# Main.net
KiCad netlist of a schematic drawn in Altium Designer
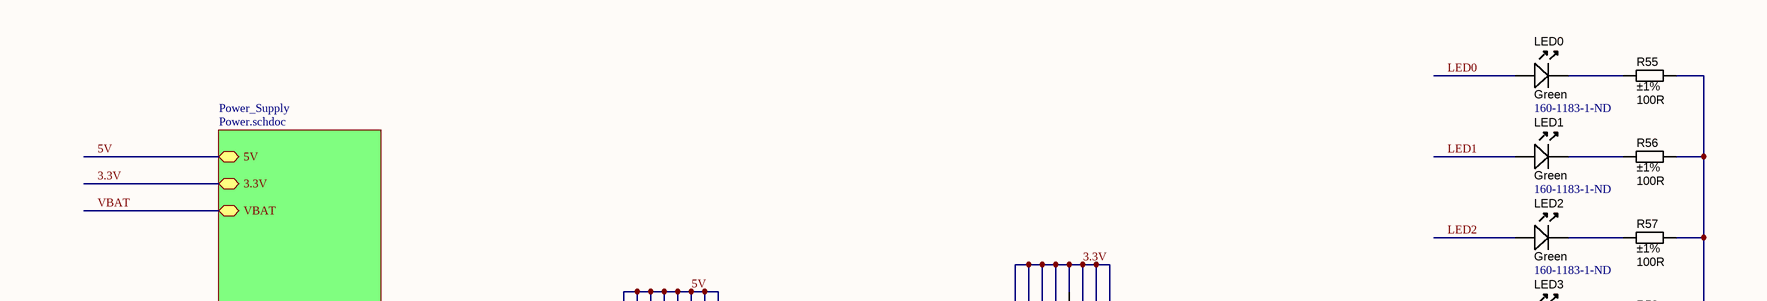
[diagram p0: Main.SchDoc, top right]
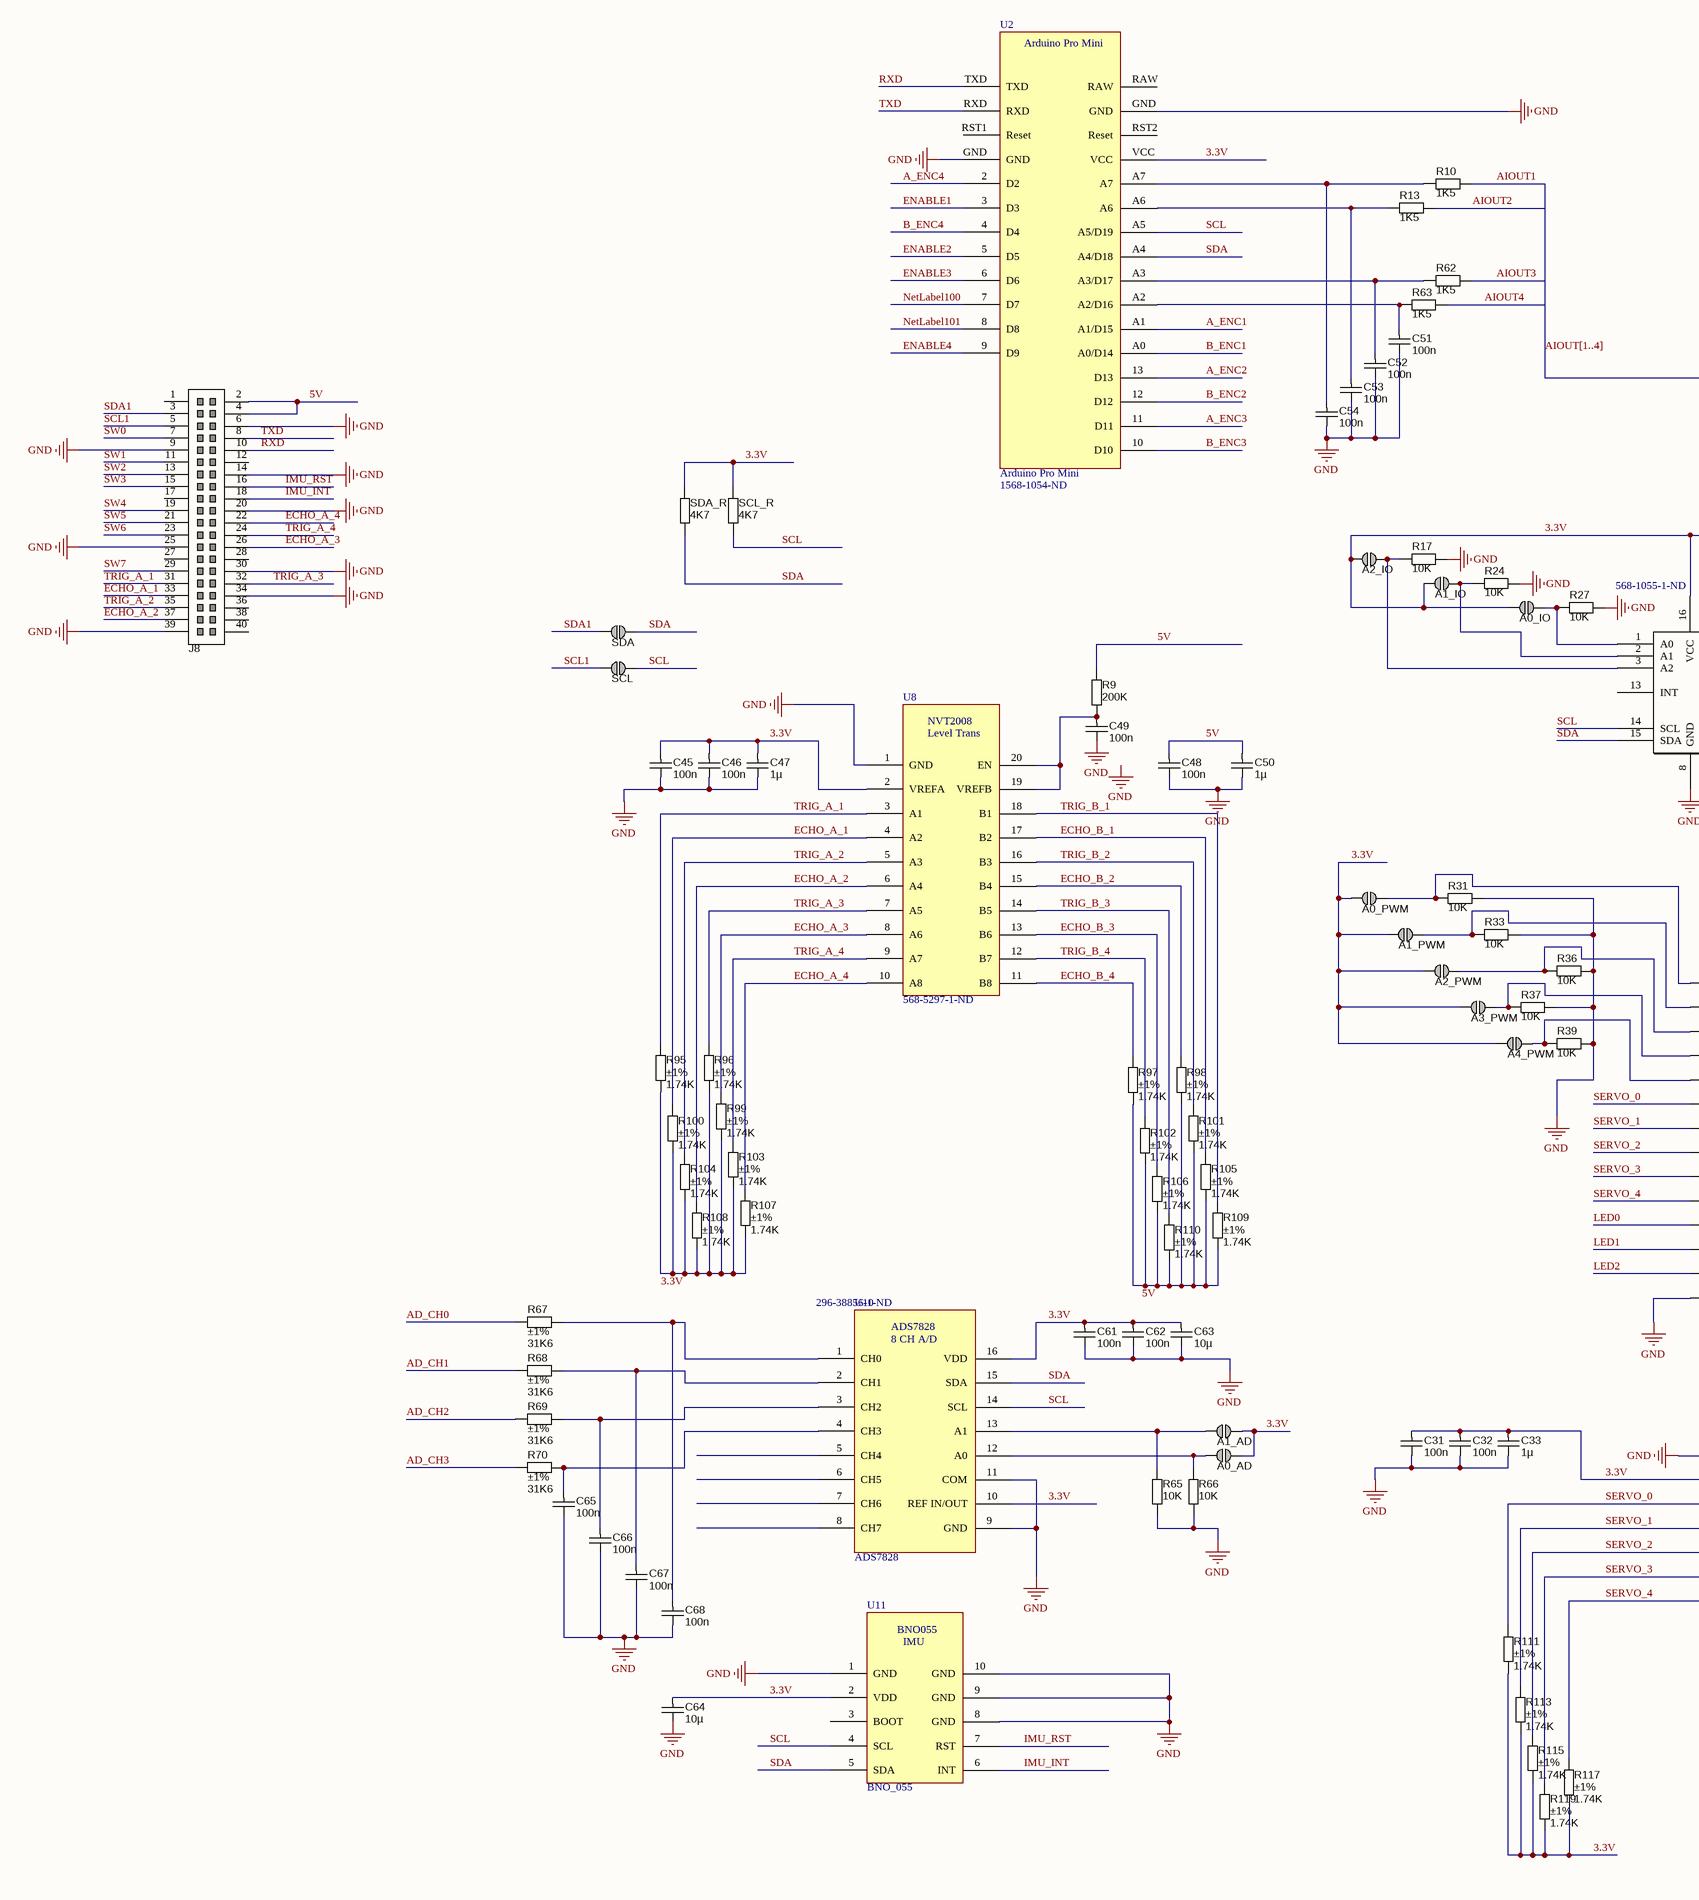
[diagram p1: Main.SchDoc, bottom left]
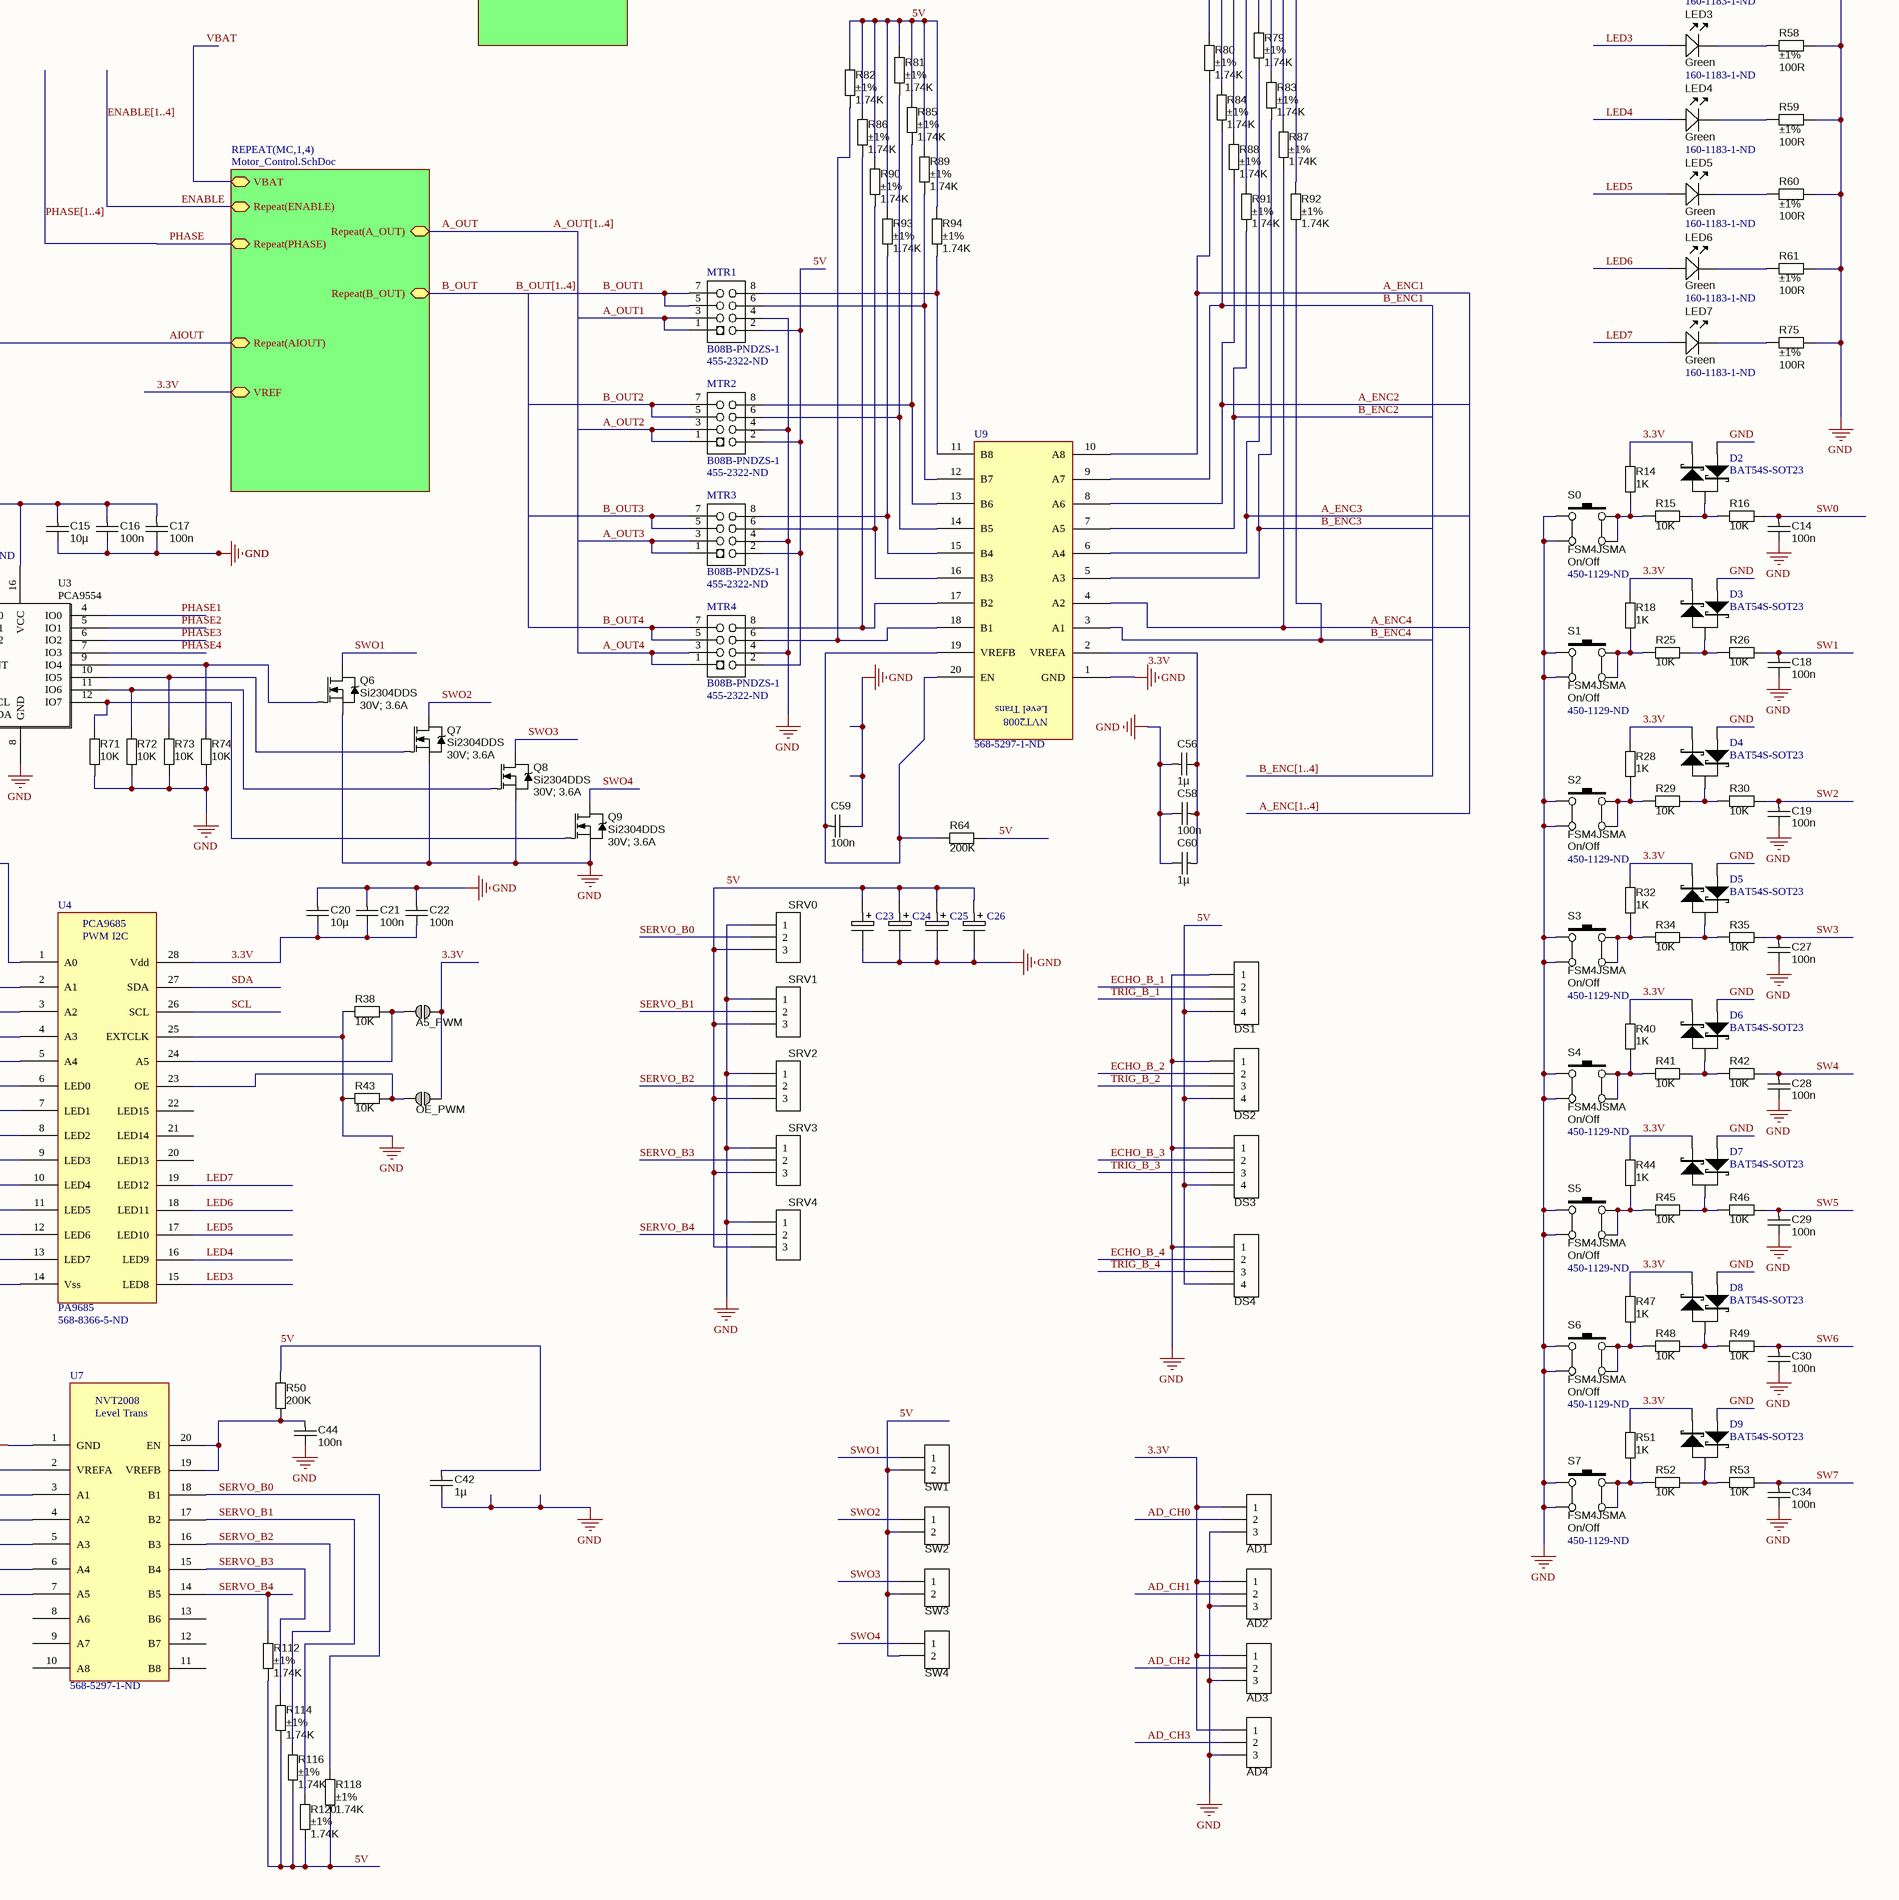
[diagram p2: Main.SchDoc, bottom right]

(export (version "E")
  (design (tool "Eeschema 10.0.6"))
  (components
    (comp (ref "A0_AD")
      (value "Jumper")
      (footprint "JUMP1")
      (description "SMD jumper")
      (libsource (lib "PBL - Pads and Jumpers") (part "JUMP1"))
    )
    (comp (ref "A0_IO")
      (value "Jumper")
      (footprint "JUMP1")
      (description "SMD jumper")
      (libsource (lib "PBL - Pads and Jumpers") (part "JUMP1"))
    )
    (comp (ref "A0_PWM")
      (value "Jumper")
      (footprint "JUMP1")
      (description "SMD jumper")
      (libsource (lib "PBL - Pads and Jumpers") (part "JUMP1"))
    )
    (comp (ref "A1_AD")
      (value "Jumper")
      (footprint "JUMP1")
      (description "SMD jumper")
      (libsource (lib "PBL - Pads and Jumpers") (part "JUMP1"))
    )
    (comp (ref "A1_IO")
      (value "Jumper")
      (footprint "JUMP1")
      (description "SMD jumper")
      (libsource (lib "PBL - Pads and Jumpers") (part "JUMP1"))
    )
    (comp (ref "A1_PWM")
      (value "Jumper")
      (footprint "JUMP1")
      (description "SMD jumper")
      (libsource (lib "PBL - Pads and Jumpers") (part "JUMP1"))
    )
    (comp (ref "A2_IO")
      (value "Jumper")
      (footprint "JUMP1")
      (description "SMD jumper")
      (libsource (lib "PBL - Pads and Jumpers") (part "JUMP1"))
    )
    (comp (ref "A2_PWM")
      (value "Jumper")
      (footprint "JUMP1")
      (description "SMD jumper")
      (libsource (lib "PBL - Pads and Jumpers") (part "JUMP1"))
    )
    (comp (ref "A3_PWM")
      (value "Jumper")
      (footprint "JUMP1")
      (description "SMD jumper")
      (libsource (lib "PBL - Pads and Jumpers") (part "JUMP1"))
    )
    (comp (ref "A4_PWM")
      (value "Jumper")
      (footprint "JUMP1")
      (description "SMD jumper")
      (libsource (lib "PBL - Pads and Jumpers") (part "JUMP1"))
    )
    (comp (ref "A5_PWM")
      (value "Jumper")
      (footprint "JUMP1")
      (description "SMD jumper")
      (libsource (lib "PBL - Pads and Jumpers") (part "JUMP1"))
    )
    (comp (ref "AD1")
      (value "JST_PH_B3B")
      (footprint "JST_PH_3_B3B")
      (description "2mm Pitch")
      (libsource (lib "PBL - Connectors") (part "JST_PH_B3B"))
    )
    (comp (ref "AD2")
      (value "JST_PH_B3B")
      (footprint "JST_PH_3_B3B")
      (description "2mm Pitch")
      (libsource (lib "PBL - Connectors") (part "JST_PH_B3B"))
    )
    (comp (ref "AD3")
      (value "JST_PH_B3B")
      (footprint "JST_PH_3_B3B")
      (description "2mm Pitch")
      (libsource (lib "PBL - Connectors") (part "JST_PH_B3B"))
    )
    (comp (ref "AD4")
      (value "JST_PH_B3B")
      (footprint "JST_PH_3_B3B")
      (description "2mm Pitch")
      (libsource (lib "PBL - Connectors") (part "JST_PH_B3B"))
    )
    (comp (ref "C14")
      (value "100n")
      (footprint "CAPC1608X90N")
      (description "Capacitor SMD Cer 100nF 10% 50V X7R 0603")
      (fields (field (name "TOLERANCE") "±10%") (field (name "Comment") "approved sub OK"))
      (libsource (lib "PBL - Capacitors") (part "CAPC_100n_0603_X7R_50V_10%"))
    )
    (comp (ref "C15")
      (value "10µ")
      (footprint "CAPC2012X135N")
      (description "Capacitor SMD Cer 10uF 10% 10V X5R 0805")
      (fields (field (name "TOLERANCE") "±10%") (field (name "Comment") "approved sub OK"))
      (libsource (lib "PBL - Capacitors") (part "CAPC_10u_0805_10V"))
    )
    (comp (ref "C16")
      (value "100n")
      (footprint "CAPC1608X90N")
      (description "Capacitor SMD Cer 100nF 10% 50V X7R 0603")
      (fields (field (name "TOLERANCE") "±10%") (field (name "Comment") "approved sub OK"))
      (libsource (lib "PBL - Capacitors") (part "CAPC_100n_0603_X7R_50V_10%"))
    )
    (comp (ref "C17")
      (value "100n")
      (footprint "CAPC1608X90N")
      (description "Capacitor SMD Cer 100nF 10% 50V X7R 0603")
      (fields (field (name "TOLERANCE") "±10%") (field (name "Comment") "approved sub OK"))
      (libsource (lib "PBL - Capacitors") (part "CAPC_100n_0603_X7R_50V_10%"))
    )
    (comp (ref "C18")
      (value "100n")
      (footprint "CAPC1608X90N")
      (description "Capacitor SMD Cer 100nF 10% 50V X7R 0603")
      (fields (field (name "TOLERANCE") "±10%") (field (name "Comment") "approved sub OK"))
      (libsource (lib "PBL - Capacitors") (part "CAPC_100n_0603_X7R_50V_10%"))
    )
    (comp (ref "C19")
      (value "100n")
      (footprint "CAPC1608X90N")
      (description "Capacitor SMD Cer 100nF 10% 50V X7R 0603")
      (fields (field (name "TOLERANCE") "±10%") (field (name "Comment") "approved sub OK"))
      (libsource (lib "PBL - Capacitors") (part "CAPC_100n_0603_X7R_50V_10%"))
    )
    (comp (ref "C20")
      (value "10µ")
      (footprint "CAPC2012X135N")
      (description "Capacitor SMD Cer 10uF 10% 10V X5R 0805")
      (fields (field (name "TOLERANCE") "±10%") (field (name "Comment") "approved sub OK"))
      (libsource (lib "PBL - Capacitors") (part "CAPC_10u_0805_10V"))
    )
    (comp (ref "C21")
      (value "100n")
      (footprint "CAPC1608X90N")
      (description "Capacitor SMD Cer 100nF 10% 50V X7R 0603")
      (fields (field (name "TOLERANCE") "±10%") (field (name "Comment") "approved sub OK"))
      (libsource (lib "PBL - Capacitors") (part "CAPC_100n_0603_X7R_50V_10%"))
    )
    (comp (ref "C22")
      (value "100n")
      (footprint "CAPC1608X90N")
      (description "Capacitor SMD Cer 100nF 10% 50V X7R 0603")
      (fields (field (name "TOLERANCE") "±10%") (field (name "Comment") "approved sub OK"))
      (libsource (lib "PBL - Capacitors") (part "CAPC_100n_0603_X7R_50V_10%"))
    )
    (comp (ref "C23")
      (value "UUD1C221MCL1GS")
      (footprint "NICH 6.3mm 7.7mm")
      (description "GENERIC CAPACITOR POLARISED")
      (libsource (lib "SMD Capacitors Electrolytic") (part "NICHICON_220uF_16V"))
    )
    (comp (ref "C24")
      (value "UUD1C221MCL1GS")
      (footprint "NICH 6.3mm 7.7mm")
      (description "GENERIC CAPACITOR POLARISED")
      (libsource (lib "SMD Capacitors Electrolytic") (part "NICHICON_220uF_16V"))
    )
    (comp (ref "C25")
      (value "UUD1C221MCL1GS")
      (footprint "NICH 6.3mm 7.7mm")
      (description "GENERIC CAPACITOR POLARISED")
      (libsource (lib "SMD Capacitors Electrolytic") (part "NICHICON_220uF_16V"))
    )
    (comp (ref "C26")
      (value "UUD1C221MCL1GS")
      (footprint "NICH 6.3mm 7.7mm")
      (description "GENERIC CAPACITOR POLARISED")
      (libsource (lib "SMD Capacitors Electrolytic") (part "NICHICON_220uF_16V"))
    )
    (comp (ref "C27")
      (value "100n")
      (footprint "CAPC1608X90N")
      (description "Capacitor SMD Cer 100nF 10% 50V X7R 0603")
      (fields (field (name "TOLERANCE") "±10%") (field (name "Comment") "approved sub OK"))
      (libsource (lib "PBL - Capacitors") (part "CAPC_100n_0603_X7R_50V_10%"))
    )
    (comp (ref "C28")
      (value "100n")
      (footprint "CAPC1608X90N")
      (description "Capacitor SMD Cer 100nF 10% 50V X7R 0603")
      (fields (field (name "TOLERANCE") "±10%") (field (name "Comment") "approved sub OK"))
      (libsource (lib "PBL - Capacitors") (part "CAPC_100n_0603_X7R_50V_10%"))
    )
    (comp (ref "C29")
      (value "100n")
      (footprint "CAPC1608X90N")
      (description "Capacitor SMD Cer 100nF 10% 50V X7R 0603")
      (fields (field (name "TOLERANCE") "±10%") (field (name "Comment") "approved sub OK"))
      (libsource (lib "PBL - Capacitors") (part "CAPC_100n_0603_X7R_50V_10%"))
    )
    (comp (ref "C30")
      (value "100n")
      (footprint "CAPC1608X90N")
      (description "Capacitor SMD Cer 100nF 10% 50V X7R 0603")
      (fields (field (name "TOLERANCE") "±10%") (field (name "Comment") "approved sub OK"))
      (libsource (lib "PBL - Capacitors") (part "CAPC_100n_0603_X7R_50V_10%"))
    )
    (comp (ref "C31")
      (value "100n")
      (footprint "CAPC1608X90N")
      (description "Capacitor SMD Cer 100nF 10% 50V X7R 0603")
      (fields (field (name "TOLERANCE") "±10%") (field (name "Comment") "approved sub OK"))
      (libsource (lib "PBL - Capacitors") (part "CAPC_100n_0603_X7R_50V_10%"))
    )
    (comp (ref "C32")
      (value "100n")
      (footprint "CAPC1608X90N")
      (description "Capacitor SMD Cer 100nF 10% 50V X7R 0603")
      (fields (field (name "TOLERANCE") "±10%") (field (name "Comment") "approved sub OK"))
      (libsource (lib "PBL - Capacitors") (part "CAPC_100n_0603_X7R_50V_10%"))
    )
    (comp (ref "C33")
      (value "1µ")
      (footprint "CAPC1608X90N")
      (description "Capacitor SMD Cer 1uF 10% 16V X7R 0603")
      (fields (field (name "TOLERANCE") "±10%") (field (name "Comment") "approved sub OK"))
      (libsource (lib "PBL - Capacitors") (part "CAPC_1u_0603_X7R_16V_10%"))
    )
    (comp (ref "C34")
      (value "100n")
      (footprint "CAPC1608X90N")
      (description "Capacitor SMD Cer 100nF 10% 50V X7R 0603")
      (fields (field (name "TOLERANCE") "±10%") (field (name "Comment") "approved sub OK"))
      (libsource (lib "PBL - Capacitors") (part "CAPC_100n_0603_X7R_50V_10%"))
    )
    (comp (ref "C42")
      (value "1µ")
      (footprint "CAPC1608X90N")
      (description "Capacitor SMD Cer 1uF 10% 16V X7R 0603")
      (fields (field (name "TOLERANCE") "±10%") (field (name "Comment") "approved sub OK"))
      (libsource (lib "PBL - Capacitors") (part "CAPC_1u_0603_X7R_16V_10%"))
    )
    (comp (ref "C44")
      (value "100n")
      (footprint "CAPC1608X90N")
      (description "Capacitor SMD Cer 100nF 10% 50V X7R 0603")
      (fields (field (name "TOLERANCE") "±10%") (field (name "Comment") "approved sub OK"))
      (libsource (lib "PBL - Capacitors") (part "CAPC_100n_0603_X7R_50V_10%"))
    )
    (comp (ref "C45")
      (value "100n")
      (footprint "CAPC1608X90N")
      (description "Capacitor SMD Cer 100nF 10% 50V X7R 0603")
      (fields (field (name "TOLERANCE") "±10%") (field (name "Comment") "approved sub OK"))
      (libsource (lib "PBL - Capacitors") (part "CAPC_100n_0603_X7R_50V_10%"))
    )
    (comp (ref "C46")
      (value "100n")
      (footprint "CAPC1608X90N")
      (description "Capacitor SMD Cer 100nF 10% 50V X7R 0603")
      (fields (field (name "TOLERANCE") "±10%") (field (name "Comment") "approved sub OK"))
      (libsource (lib "PBL - Capacitors") (part "CAPC_100n_0603_X7R_50V_10%"))
    )
    (comp (ref "C47")
      (value "1µ")
      (footprint "CAPC1608X90N")
      (description "Capacitor SMD Cer 1uF 10% 16V X7R 0603")
      (fields (field (name "TOLERANCE") "±10%") (field (name "Comment") "approved sub OK"))
      (libsource (lib "PBL - Capacitors") (part "CAPC_1u_0603_X7R_16V_10%"))
    )
    (comp (ref "C48")
      (value "100n")
      (footprint "CAPC1608X90N")
      (description "Capacitor SMD Cer 100nF 10% 50V X7R 0603")
      (fields (field (name "TOLERANCE") "±10%") (field (name "Comment") "approved sub OK"))
      (libsource (lib "PBL - Capacitors") (part "CAPC_100n_0603_X7R_50V_10%"))
    )
    (comp (ref "C49")
      (value "100n")
      (footprint "CAPC1608X90N")
      (description "Capacitor SMD Cer 100nF 10% 50V X7R 0603")
      (fields (field (name "TOLERANCE") "±10%") (field (name "Comment") "approved sub OK"))
      (libsource (lib "PBL - Capacitors") (part "CAPC_100n_0603_X7R_50V_10%"))
    )
    (comp (ref "C50")
      (value "1µ")
      (footprint "CAPC1608X90N")
      (description "Capacitor SMD Cer 1uF 10% 16V X7R 0603")
      (fields (field (name "TOLERANCE") "±10%") (field (name "Comment") "approved sub OK"))
      (libsource (lib "PBL - Capacitors") (part "CAPC_1u_0603_X7R_16V_10%"))
    )
    (comp (ref "C51")
      (value "100n")
      (footprint "CAPC1608X90N")
      (description "Capacitor SMD Cer 100nF 10% 50V X7R 0603")
      (fields (field (name "TOLERANCE") "±10%") (field (name "Comment") "approved sub OK"))
      (libsource (lib "PBL - Capacitors") (part "CAPC_100n_0603_X7R_50V_10%"))
    )
    (comp (ref "C52")
      (value "100n")
      (footprint "CAPC1608X90N")
      (description "Capacitor SMD Cer 100nF 10% 50V X7R 0603")
      (fields (field (name "TOLERANCE") "±10%") (field (name "Comment") "approved sub OK"))
      (libsource (lib "PBL - Capacitors") (part "CAPC_100n_0603_X7R_50V_10%"))
    )
    (comp (ref "C53")
      (value "100n")
      (footprint "CAPC1608X90N")
      (description "Capacitor SMD Cer 100nF 10% 50V X7R 0603")
      (fields (field (name "TOLERANCE") "±10%") (field (name "Comment") "approved sub OK"))
      (libsource (lib "PBL - Capacitors") (part "CAPC_100n_0603_X7R_50V_10%"))
    )
    (comp (ref "C54")
      (value "100n")
      (footprint "CAPC1608X90N")
      (description "Capacitor SMD Cer 100nF 10% 50V X7R 0603")
      (fields (field (name "TOLERANCE") "±10%") (field (name "Comment") "approved sub OK"))
      (libsource (lib "PBL - Capacitors") (part "CAPC_100n_0603_X7R_50V_10%"))
    )
    (comp (ref "C56")
      (value "1µ")
      (footprint "CAPC1608X90N")
      (description "Capacitor SMD Cer 1uF 10% 16V X7R 0603")
      (fields (field (name "TOLERANCE") "±10%") (field (name "Comment") "approved sub OK"))
      (libsource (lib "PBL - Capacitors") (part "CAPC_1u_0603_X7R_16V_10%"))
    )
    (comp (ref "C58")
      (value "100n")
      (footprint "CAPC1608X90N")
      (description "Capacitor SMD Cer 100nF 10% 50V X7R 0603")
      (fields (field (name "TOLERANCE") "±10%") (field (name "Comment") "approved sub OK"))
      (libsource (lib "PBL - Capacitors") (part "CAPC_100n_0603_X7R_50V_10%"))
    )
    (comp (ref "C59")
      (value "100n")
      (footprint "CAPC1608X90N")
      (description "Capacitor SMD Cer 100nF 10% 50V X7R 0603")
      (fields (field (name "TOLERANCE") "±10%") (field (name "Comment") "approved sub OK"))
      (libsource (lib "PBL - Capacitors") (part "CAPC_100n_0603_X7R_50V_10%"))
    )
    (comp (ref "C60")
      (value "1µ")
      (footprint "CAPC1608X90N")
      (description "Capacitor SMD Cer 1uF 10% 16V X7R 0603")
      (fields (field (name "TOLERANCE") "±10%") (field (name "Comment") "approved sub OK"))
      (libsource (lib "PBL - Capacitors") (part "CAPC_1u_0603_X7R_16V_10%"))
    )
    (comp (ref "C61")
      (value "100n")
      (footprint "CAPC1608X90N")
      (description "Capacitor SMD Cer 100nF 10% 50V X7R 0603")
      (fields (field (name "TOLERANCE") "±10%") (field (name "Comment") "approved sub OK"))
      (libsource (lib "PBL - Capacitors") (part "CAPC_100n_0603_X7R_50V_10%"))
    )
    (comp (ref "C62")
      (value "100n")
      (footprint "CAPC1608X90N")
      (description "Capacitor SMD Cer 100nF 10% 50V X7R 0603")
      (fields (field (name "TOLERANCE") "±10%") (field (name "Comment") "approved sub OK"))
      (libsource (lib "PBL - Capacitors") (part "CAPC_100n_0603_X7R_50V_10%"))
    )
    (comp (ref "C63")
      (value "10µ")
      (footprint "CAPC2012X135N")
      (description "Capacitor SMD Cer 10uF 10% 10V X5R 0805")
      (fields (field (name "TOLERANCE") "±10%") (field (name "Comment") "approved sub OK"))
      (libsource (lib "PBL - Capacitors") (part "CAPC_10u_0805_10V"))
    )
    (comp (ref "C64")
      (value "10µ")
      (footprint "CAPC2012X135N")
      (description "Capacitor SMD Cer 10uF 10% 10V X5R 0805")
      (fields (field (name "TOLERANCE") "±10%") (field (name "Comment") "approved sub OK"))
      (libsource (lib "PBL - Capacitors") (part "CAPC_10u_0805_10V"))
    )
    (comp (ref "C65")
      (value "100n")
      (footprint "CAPC1608X90N")
      (description "Capacitor SMD Cer 100nF 10% 50V X7R 0603")
      (fields (field (name "TOLERANCE") "±10%") (field (name "Comment") "approved sub OK"))
      (libsource (lib "PBL - Capacitors") (part "CAPC_100n_0603_X7R_50V_10%"))
    )
    (comp (ref "C66")
      (value "100n")
      (footprint "CAPC1608X90N")
      (description "Capacitor SMD Cer 100nF 10% 50V X7R 0603")
      (fields (field (name "TOLERANCE") "±10%") (field (name "Comment") "approved sub OK"))
      (libsource (lib "PBL - Capacitors") (part "CAPC_100n_0603_X7R_50V_10%"))
    )
    (comp (ref "C67")
      (value "100n")
      (footprint "CAPC1608X90N")
      (description "Capacitor SMD Cer 100nF 10% 50V X7R 0603")
      (fields (field (name "TOLERANCE") "±10%") (field (name "Comment") "approved sub OK"))
      (libsource (lib "PBL - Capacitors") (part "CAPC_100n_0603_X7R_50V_10%"))
    )
    (comp (ref "C68")
      (value "100n")
      (footprint "CAPC1608X90N")
      (description "Capacitor SMD Cer 100nF 10% 50V X7R 0603")
      (fields (field (name "TOLERANCE") "±10%") (field (name "Comment") "approved sub OK"))
      (libsource (lib "PBL - Capacitors") (part "CAPC_100n_0603_X7R_50V_10%"))
    )
    (comp (ref "D2")
      (value "BAT54S-SOT23")
      (footprint "SOT23-123")
      (description "DUAL SCHOTTKY DIODE SERIES")
      (fields
        (field (name "MANUFACTURER PART NUMBER") "BAT54S,215")
        (field (name "MANUFACTURER") "NXP Semiconductors")
      )
      (libsource (lib "SMD Diodes") (part "BAT54S-SOT23"))
    )
    (comp (ref "D3")
      (value "BAT54S-SOT23")
      (footprint "SOT23-123")
      (description "DUAL SCHOTTKY DIODE SERIES")
      (fields
        (field (name "MANUFACTURER PART NUMBER") "BAT54S,215")
        (field (name "MANUFACTURER") "NXP Semiconductors")
      )
      (libsource (lib "SMD Diodes") (part "BAT54S-SOT23"))
    )
    (comp (ref "D4")
      (value "BAT54S-SOT23")
      (footprint "SOT23-123")
      (description "DUAL SCHOTTKY DIODE SERIES")
      (fields
        (field (name "MANUFACTURER PART NUMBER") "BAT54S,215")
        (field (name "MANUFACTURER") "NXP Semiconductors")
      )
      (libsource (lib "SMD Diodes") (part "BAT54S-SOT23"))
    )
    (comp (ref "D5")
      (value "BAT54S-SOT23")
      (footprint "SOT23-123")
      (description "DUAL SCHOTTKY DIODE SERIES")
      (fields
        (field (name "MANUFACTURER PART NUMBER") "BAT54S,215")
        (field (name "MANUFACTURER") "NXP Semiconductors")
      )
      (libsource (lib "SMD Diodes") (part "BAT54S-SOT23"))
    )
    (comp (ref "D6")
      (value "BAT54S-SOT23")
      (footprint "SOT23-123")
      (description "DUAL SCHOTTKY DIODE SERIES")
      (fields
        (field (name "MANUFACTURER PART NUMBER") "BAT54S,215")
        (field (name "MANUFACTURER") "NXP Semiconductors")
      )
      (libsource (lib "SMD Diodes") (part "BAT54S-SOT23"))
    )
    (comp (ref "D7")
      (value "BAT54S-SOT23")
      (footprint "SOT23-123")
      (description "DUAL SCHOTTKY DIODE SERIES")
      (fields
        (field (name "MANUFACTURER PART NUMBER") "BAT54S,215")
        (field (name "MANUFACTURER") "NXP Semiconductors")
      )
      (libsource (lib "SMD Diodes") (part "BAT54S-SOT23"))
    )
    (comp (ref "D8")
      (value "BAT54S-SOT23")
      (footprint "SOT23-123")
      (description "DUAL SCHOTTKY DIODE SERIES")
      (fields
        (field (name "MANUFACTURER PART NUMBER") "BAT54S,215")
        (field (name "MANUFACTURER") "NXP Semiconductors")
      )
      (libsource (lib "SMD Diodes") (part "BAT54S-SOT23"))
    )
    (comp (ref "D9")
      (value "BAT54S-SOT23")
      (footprint "SOT23-123")
      (description "DUAL SCHOTTKY DIODE SERIES")
      (fields
        (field (name "MANUFACTURER PART NUMBER") "BAT54S,215")
        (field (name "MANUFACTURER") "NXP Semiconductors")
      )
      (libsource (lib "SMD Diodes") (part "BAT54S-SOT23"))
    )
    (comp (ref "DS1")
      (value "JST_PH_B4B")
      (footprint "JST_PH_4_B4B")
      (description "2mm Pitch")
      (libsource (lib "PBL - Connectors") (part "JST_PH_B4B"))
    )
    (comp (ref "DS2")
      (value "JST_PH_B4B")
      (footprint "JST_PH_4_B4B")
      (description "2mm Pitch")
      (libsource (lib "PBL - Connectors") (part "JST_PH_B4B"))
    )
    (comp (ref "DS3")
      (value "JST_PH_B4B")
      (footprint "JST_PH_4_B4B")
      (description "2mm Pitch")
      (libsource (lib "PBL - Connectors") (part "JST_PH_B4B"))
    )
    (comp (ref "DS4")
      (value "JST_PH_B4B")
      (footprint "JST_PH_4_B4B")
      (description "2mm Pitch")
      (libsource (lib "PBL - Connectors") (part "JST_PH_B4B"))
    )
    (comp (ref "J8")
      (value "2223")
      (footprint "40P_PCB_SOCKET_BRD_MNT  REVERSE")
      (description "40 Position Header Connector 0.100\" (2.54mm) Through Hole Gold")
      (libsource (lib "PBL - Connectors") (part "CONN_SOCKET_2x20P_0.100in  Rpi Female"))
    )
    (comp (ref "LED0")
      (value "Green")
      (footprint "LED-0603-GREEN")
      (description "LED 0603 SMD Green 525nm 350mcd 20mA")
      (fields (field (name "SUPPLIER PART NUMBER 1") "160-1183-1-ND"))
      (libsource (lib "PBL - Light Sources") (part "LED_SMD_Green_0603_525nm_350mcd"))
    )
    (comp (ref "LED1")
      (value "Green")
      (footprint "LED-0603-GREEN")
      (description "LED 0603 SMD Green 525nm 350mcd 20mA")
      (fields (field (name "SUPPLIER PART NUMBER 1") "160-1183-1-ND"))
      (libsource (lib "PBL - Light Sources") (part "LED_SMD_Green_0603_525nm_350mcd"))
    )
    (comp (ref "LED2")
      (value "Green")
      (footprint "LED-0603-GREEN")
      (description "LED 0603 SMD Green 525nm 350mcd 20mA")
      (fields (field (name "SUPPLIER PART NUMBER 1") "160-1183-1-ND"))
      (libsource (lib "PBL - Light Sources") (part "LED_SMD_Green_0603_525nm_350mcd"))
    )
    (comp (ref "LED3")
      (value "Green")
      (footprint "LED-0603-GREEN")
      (description "LED 0603 SMD Green 525nm 350mcd 20mA")
      (fields (field (name "SUPPLIER PART NUMBER 1") "160-1183-1-ND"))
      (libsource (lib "PBL - Light Sources") (part "LED_SMD_Green_0603_525nm_350mcd"))
    )
    (comp (ref "LED4")
      (value "Green")
      (footprint "LED-0603-GREEN")
      (description "LED 0603 SMD Green 525nm 350mcd 20mA")
      (fields (field (name "SUPPLIER PART NUMBER 1") "160-1183-1-ND"))
      (libsource (lib "PBL - Light Sources") (part "LED_SMD_Green_0603_525nm_350mcd"))
    )
    (comp (ref "LED5")
      (value "Green")
      (footprint "LED-0603-GREEN")
      (description "LED 0603 SMD Green 525nm 350mcd 20mA")
      (fields (field (name "SUPPLIER PART NUMBER 1") "160-1183-1-ND"))
      (libsource (lib "PBL - Light Sources") (part "LED_SMD_Green_0603_525nm_350mcd"))
    )
    (comp (ref "LED6")
      (value "Green")
      (footprint "LED-0603-GREEN")
      (description "LED 0603 SMD Green 525nm 350mcd 20mA")
      (fields (field (name "SUPPLIER PART NUMBER 1") "160-1183-1-ND"))
      (libsource (lib "PBL - Light Sources") (part "LED_SMD_Green_0603_525nm_350mcd"))
    )
    (comp (ref "LED7")
      (value "Green")
      (footprint "LED-0603-GREEN")
      (description "LED 0603 SMD Green 525nm 350mcd 20mA")
      (fields (field (name "SUPPLIER PART NUMBER 1") "160-1183-1-ND"))
      (libsource (lib "PBL - Light Sources") (part "LED_SMD_Green_0603_525nm_350mcd"))
    )
    (comp (ref "MTR1")
      (value "B08B-PNDZS-1")
      (footprint "JST PND 8 Pin")
      (fields (field (name "SUPPLIER PART NUMBER 1") "455-2322-ND"))
      (libsource (lib "TH Connectors") (part "JST PND 8 PIN"))
    )
    (comp (ref "MTR2")
      (value "B08B-PNDZS-1")
      (footprint "JST PND 8 Pin")
      (fields (field (name "SUPPLIER PART NUMBER 1") "455-2322-ND"))
      (libsource (lib "TH Connectors") (part "JST PND 8 PIN"))
    )
    (comp (ref "MTR3")
      (value "B08B-PNDZS-1")
      (footprint "JST PND 8 Pin")
      (fields (field (name "SUPPLIER PART NUMBER 1") "455-2322-ND"))
      (libsource (lib "TH Connectors") (part "JST PND 8 PIN"))
    )
    (comp (ref "MTR4")
      (value "B08B-PNDZS-1")
      (footprint "JST PND 8 Pin")
      (fields (field (name "SUPPLIER PART NUMBER 1") "455-2322-ND"))
      (libsource (lib "TH Connectors") (part "JST PND 8 PIN"))
    )
    (comp (ref "OE_PWM")
      (value "Jumper")
      (footprint "JUMP1")
      (description "SMD jumper")
      (libsource (lib "PBL - Pads and Jumpers") (part "JUMP1"))
    )
    (comp (ref "Q6")
      (value "Si2304DDS")
      (footprint "SOT23-3")
      (description "MOSFET SMD N-CH 30V 3.6A 1.7W SOT23-3")
      (fields (field (name "RATINGS") "30V; 3.6A"))
      (libsource (lib "RyanMasterLib") (part "MOSFET_Si2304DDS"))
    )
    (comp (ref "Q7")
      (value "Si2304DDS")
      (footprint "SOT23-3")
      (description "MOSFET SMD N-CH 30V 3.6A 1.7W SOT23-3")
      (fields (field (name "RATINGS") "30V; 3.6A"))
      (libsource (lib "RyanMasterLib") (part "MOSFET_Si2304DDS"))
    )
    (comp (ref "Q8")
      (value "Si2304DDS")
      (footprint "SOT23-3")
      (description "MOSFET SMD N-CH 30V 3.6A 1.7W SOT23-3")
      (fields (field (name "RATINGS") "30V; 3.6A"))
      (libsource (lib "RyanMasterLib") (part "MOSFET_Si2304DDS"))
    )
    (comp (ref "Q9")
      (value "Si2304DDS")
      (footprint "SOT23-3")
      (description "MOSFET SMD N-CH 30V 3.6A 1.7W SOT23-3")
      (fields (field (name "RATINGS") "30V; 3.6A"))
      (libsource (lib "RyanMasterLib") (part "MOSFET_Si2304DDS"))
    )
    (comp (ref "R9")
      (value "200K")
      (footprint "RESC1608X55N")
      (description "Resistor SMD chip 200K Ohm 0.1W 5% 0603")
      (fields (field (name "TOLERANCE") "±5%") (field (name "Comment") "Thick Film"))
      (libsource (lib "PBL - Resistors") (part "RES_200K_0603_5%"))
    )
    (comp (ref "R10")
      (value "1K5")
      (footprint "RESC1608X55N")
      (description "Resistor SMD chip 1.5k Ohm 0.1W 5% 0603")
      (fields (field (name "TOLERANCE") "±5%") (field (name "Comment") "Thick Film"))
      (libsource (lib "PBL - Resistors") (part "RES_1K5_0603_5%"))
    )
    (comp (ref "R13")
      (value "1K5")
      (footprint "RESC1608X55N")
      (description "Resistor SMD chip 1.5k Ohm 0.1W 5% 0603")
      (fields (field (name "TOLERANCE") "±5%") (field (name "Comment") "Thick Film"))
      (libsource (lib "PBL - Resistors") (part "RES_1K5_0603_5%"))
    )
    (comp (ref "R14")
      (value "1K")
      (footprint "RESC1608X55N")
      (description "Resistor SMD chip 1k Ohm 0.1W 5% 0603")
      (fields (field (name "TOLERANCE") "±5%") (field (name "Comment") "Thick Film"))
      (libsource (lib "PBL - Resistors") (part "RES_1K_0603_5%"))
    )
    (comp (ref "R15")
      (value "10K")
      (footprint "RESC1608X55N")
      (description "Resistor SMD chip 10k Ohm 0.1W 5% 0603")
      (fields (field (name "TOLERANCE") "±5%") (field (name "Comment") "Thick Film"))
      (libsource (lib "PBL - Resistors") (part "RES_10K_0603_5%"))
    )
    (comp (ref "R16")
      (value "10K")
      (footprint "RESC1608X55N")
      (description "Resistor SMD chip 10k Ohm 0.1W 5% 0603")
      (fields (field (name "TOLERANCE") "±5%") (field (name "Comment") "Thick Film"))
      (libsource (lib "PBL - Resistors") (part "RES_10K_0603_5%"))
    )
    (comp (ref "R17")
      (value "10K")
      (footprint "RESC1608X55N")
      (description "Resistor SMD chip 10k Ohm 0.1W 5% 0603")
      (fields (field (name "TOLERANCE") "±5%") (field (name "Comment") "Thick Film"))
      (libsource (lib "PBL - Resistors") (part "RES_10K_0603_5%"))
    )
    (comp (ref "R18")
      (value "1K")
      (footprint "RESC1608X55N")
      (description "Resistor SMD chip 1k Ohm 0.1W 5% 0603")
      (fields (field (name "TOLERANCE") "±5%") (field (name "Comment") "Thick Film"))
      (libsource (lib "PBL - Resistors") (part "RES_1K_0603_5%"))
    )
    (comp (ref "R24")
      (value "10K")
      (footprint "RESC1608X55N")
      (description "Resistor SMD chip 10k Ohm 0.1W 5% 0603")
      (fields (field (name "TOLERANCE") "±5%") (field (name "Comment") "Thick Film"))
      (libsource (lib "PBL - Resistors") (part "RES_10K_0603_5%"))
    )
    (comp (ref "R25")
      (value "10K")
      (footprint "RESC1608X55N")
      (description "Resistor SMD chip 10k Ohm 0.1W 5% 0603")
      (fields (field (name "TOLERANCE") "±5%") (field (name "Comment") "Thick Film"))
      (libsource (lib "PBL - Resistors") (part "RES_10K_0603_5%"))
    )
    (comp (ref "R26")
      (value "10K")
      (footprint "RESC1608X55N")
      (description "Resistor SMD chip 10k Ohm 0.1W 5% 0603")
      (fields (field (name "TOLERANCE") "±5%") (field (name "Comment") "Thick Film"))
      (libsource (lib "PBL - Resistors") (part "RES_10K_0603_5%"))
    )
    (comp (ref "R27")
      (value "10K")
      (footprint "RESC1608X55N")
      (description "Resistor SMD chip 10k Ohm 0.1W 5% 0603")
      (fields (field (name "TOLERANCE") "±5%") (field (name "Comment") "Thick Film"))
      (libsource (lib "PBL - Resistors") (part "RES_10K_0603_5%"))
    )
    (comp (ref "R28")
      (value "1K")
      (footprint "RESC1608X55N")
      (description "Resistor SMD chip 1k Ohm 0.1W 5% 0603")
      (fields (field (name "TOLERANCE") "±5%") (field (name "Comment") "Thick Film"))
      (libsource (lib "PBL - Resistors") (part "RES_1K_0603_5%"))
    )
    (comp (ref "R29")
      (value "10K")
      (footprint "RESC1608X55N")
      (description "Resistor SMD chip 10k Ohm 0.1W 5% 0603")
      (fields (field (name "TOLERANCE") "±5%") (field (name "Comment") "Thick Film"))
      (libsource (lib "PBL - Resistors") (part "RES_10K_0603_5%"))
    )
    (comp (ref "R30")
      (value "10K")
      (footprint "RESC1608X55N")
      (description "Resistor SMD chip 10k Ohm 0.1W 5% 0603")
      (fields (field (name "TOLERANCE") "±5%") (field (name "Comment") "Thick Film"))
      (libsource (lib "PBL - Resistors") (part "RES_10K_0603_5%"))
    )
    (comp (ref "R31")
      (value "10K")
      (footprint "RESC1608X55N")
      (description "Resistor SMD chip 10k Ohm 0.1W 5% 0603")
      (fields (field (name "TOLERANCE") "±5%") (field (name "Comment") "Thick Film"))
      (libsource (lib "PBL - Resistors") (part "RES_10K_0603_5%"))
    )
    (comp (ref "R32")
      (value "1K")
      (footprint "RESC1608X55N")
      (description "Resistor SMD chip 1k Ohm 0.1W 5% 0603")
      (fields (field (name "TOLERANCE") "±5%") (field (name "Comment") "Thick Film"))
      (libsource (lib "PBL - Resistors") (part "RES_1K_0603_5%"))
    )
    (comp (ref "R33")
      (value "10K")
      (footprint "RESC1608X55N")
      (description "Resistor SMD chip 10k Ohm 0.1W 5% 0603")
      (fields (field (name "TOLERANCE") "±5%") (field (name "Comment") "Thick Film"))
      (libsource (lib "PBL - Resistors") (part "RES_10K_0603_5%"))
    )
    (comp (ref "R34")
      (value "10K")
      (footprint "RESC1608X55N")
      (description "Resistor SMD chip 10k Ohm 0.1W 5% 0603")
      (fields (field (name "TOLERANCE") "±5%") (field (name "Comment") "Thick Film"))
      (libsource (lib "PBL - Resistors") (part "RES_10K_0603_5%"))
    )
    (comp (ref "R35")
      (value "10K")
      (footprint "RESC1608X55N")
      (description "Resistor SMD chip 10k Ohm 0.1W 5% 0603")
      (fields (field (name "TOLERANCE") "±5%") (field (name "Comment") "Thick Film"))
      (libsource (lib "PBL - Resistors") (part "RES_10K_0603_5%"))
    )
    (comp (ref "R36")
      (value "10K")
      (footprint "RESC1608X55N")
      (description "Resistor SMD chip 10k Ohm 0.1W 5% 0603")
      (fields (field (name "TOLERANCE") "±5%") (field (name "Comment") "Thick Film"))
      (libsource (lib "PBL - Resistors") (part "RES_10K_0603_5%"))
    )
    (comp (ref "R37")
      (value "10K")
      (footprint "RESC1608X55N")
      (description "Resistor SMD chip 10k Ohm 0.1W 5% 0603")
      (fields (field (name "TOLERANCE") "±5%") (field (name "Comment") "Thick Film"))
      (libsource (lib "PBL - Resistors") (part "RES_10K_0603_5%"))
    )
    (comp (ref "R38")
      (value "10K")
      (footprint "RESC1608X55N")
      (description "Resistor SMD chip 10k Ohm 0.1W 5% 0603")
      (fields (field (name "TOLERANCE") "±5%") (field (name "Comment") "Thick Film"))
      (libsource (lib "") (part "RES_10K_0603_5%_1"))
    )
    (comp (ref "R39")
      (value "10K")
      (footprint "RESC1608X55N")
      (description "Resistor SMD chip 10k Ohm 0.1W 5% 0603")
      (fields (field (name "TOLERANCE") "±5%") (field (name "Comment") "Thick Film"))
      (libsource (lib "PBL - Resistors") (part "RES_10K_0603_5%"))
    )
    (comp (ref "R40")
      (value "1K")
      (footprint "RESC1608X55N")
      (description "Resistor SMD chip 1k Ohm 0.1W 5% 0603")
      (fields (field (name "TOLERANCE") "±5%") (field (name "Comment") "Thick Film"))
      (libsource (lib "PBL - Resistors") (part "RES_1K_0603_5%"))
    )
    (comp (ref "R41")
      (value "10K")
      (footprint "RESC1608X55N")
      (description "Resistor SMD chip 10k Ohm 0.1W 5% 0603")
      (fields (field (name "TOLERANCE") "±5%") (field (name "Comment") "Thick Film"))
      (libsource (lib "PBL - Resistors") (part "RES_10K_0603_5%"))
    )
    (comp (ref "R42")
      (value "10K")
      (footprint "RESC1608X55N")
      (description "Resistor SMD chip 10k Ohm 0.1W 5% 0603")
      (fields (field (name "TOLERANCE") "±5%") (field (name "Comment") "Thick Film"))
      (libsource (lib "PBL - Resistors") (part "RES_10K_0603_5%"))
    )
    (comp (ref "R43")
      (value "10K")
      (footprint "RESC1608X55N")
      (description "Resistor SMD chip 10k Ohm 0.1W 5% 0603")
      (fields (field (name "TOLERANCE") "±5%") (field (name "Comment") "Thick Film"))
      (libsource (lib "") (part "RES_10K_0603_5%_1"))
    )
    (comp (ref "R44")
      (value "1K")
      (footprint "RESC1608X55N")
      (description "Resistor SMD chip 1k Ohm 0.1W 5% 0603")
      (fields (field (name "TOLERANCE") "±5%") (field (name "Comment") "Thick Film"))
      (libsource (lib "PBL - Resistors") (part "RES_1K_0603_5%"))
    )
    (comp (ref "R45")
      (value "10K")
      (footprint "RESC1608X55N")
      (description "Resistor SMD chip 10k Ohm 0.1W 5% 0603")
      (fields (field (name "TOLERANCE") "±5%") (field (name "Comment") "Thick Film"))
      (libsource (lib "PBL - Resistors") (part "RES_10K_0603_5%"))
    )
    (comp (ref "R46")
      (value "10K")
      (footprint "RESC1608X55N")
      (description "Resistor SMD chip 10k Ohm 0.1W 5% 0603")
      (fields (field (name "TOLERANCE") "±5%") (field (name "Comment") "Thick Film"))
      (libsource (lib "PBL - Resistors") (part "RES_10K_0603_5%"))
    )
    (comp (ref "R47")
      (value "1K")
      (footprint "RESC1608X55N")
      (description "Resistor SMD chip 1k Ohm 0.1W 5% 0603")
      (fields (field (name "TOLERANCE") "±5%") (field (name "Comment") "Thick Film"))
      (libsource (lib "PBL - Resistors") (part "RES_1K_0603_5%"))
    )
    (comp (ref "R48")
      (value "10K")
      (footprint "RESC1608X55N")
      (description "Resistor SMD chip 10k Ohm 0.1W 5% 0603")
      (fields (field (name "TOLERANCE") "±5%") (field (name "Comment") "Thick Film"))
      (libsource (lib "PBL - Resistors") (part "RES_10K_0603_5%"))
    )
    (comp (ref "R49")
      (value "10K")
      (footprint "RESC1608X55N")
      (description "Resistor SMD chip 10k Ohm 0.1W 5% 0603")
      (fields (field (name "TOLERANCE") "±5%") (field (name "Comment") "Thick Film"))
      (libsource (lib "PBL - Resistors") (part "RES_10K_0603_5%"))
    )
    (comp (ref "R50")
      (value "200K")
      (footprint "RESC1608X55N")
      (description "Resistor SMD chip 200K Ohm 0.1W 5% 0603")
      (fields (field (name "TOLERANCE") "±5%") (field (name "Comment") "Thick Film"))
      (libsource (lib "PBL - Resistors") (part "RES_200K_0603_5%"))
    )
    (comp (ref "R51")
      (value "1K")
      (footprint "RESC1608X55N")
      (description "Resistor SMD chip 1k Ohm 0.1W 5% 0603")
      (fields (field (name "TOLERANCE") "±5%") (field (name "Comment") "Thick Film"))
      (libsource (lib "PBL - Resistors") (part "RES_1K_0603_5%"))
    )
    (comp (ref "R52")
      (value "10K")
      (footprint "RESC1608X55N")
      (description "Resistor SMD chip 10k Ohm 0.1W 5% 0603")
      (fields (field (name "TOLERANCE") "±5%") (field (name "Comment") "Thick Film"))
      (libsource (lib "PBL - Resistors") (part "RES_10K_0603_5%"))
    )
    (comp (ref "R53")
      (value "10K")
      (footprint "RESC1608X55N")
      (description "Resistor SMD chip 10k Ohm 0.1W 5% 0603")
      (fields (field (name "TOLERANCE") "±5%") (field (name "Comment") "Thick Film"))
      (libsource (lib "PBL - Resistors") (part "RES_10K_0603_5%"))
    )
    (comp (ref "R55")
      (value "100R")
      (footprint "RESC1608X55N")
      (description "Resistor SMD chip 100 Ohm 0.1W 1% 0603")
      (fields (field (name "TOLERANCE") "±1%") (field (name "Comment") "Thick Film"))
      (libsource (lib "PBL - Resistors") (part "RES_100R_0603_1%"))
    )
    (comp (ref "R56")
      (value "100R")
      (footprint "RESC1608X55N")
      (description "Resistor SMD chip 100 Ohm 0.1W 1% 0603")
      (fields (field (name "TOLERANCE") "±1%") (field (name "Comment") "Thick Film"))
      (libsource (lib "PBL - Resistors") (part "RES_100R_0603_1%"))
    )
    (comp (ref "R57")
      (value "100R")
      (footprint "RESC1608X55N")
      (description "Resistor SMD chip 100 Ohm 0.1W 1% 0603")
      (fields (field (name "TOLERANCE") "±1%") (field (name "Comment") "Thick Film"))
      (libsource (lib "PBL - Resistors") (part "RES_100R_0603_1%"))
    )
    (comp (ref "R58")
      (value "100R")
      (footprint "RESC1608X55N")
      (description "Resistor SMD chip 100 Ohm 0.1W 1% 0603")
      (fields (field (name "TOLERANCE") "±1%") (field (name "Comment") "Thick Film"))
      (libsource (lib "PBL - Resistors") (part "RES_100R_0603_1%"))
    )
    (comp (ref "R59")
      (value "100R")
      (footprint "RESC1608X55N")
      (description "Resistor SMD chip 100 Ohm 0.1W 1% 0603")
      (fields (field (name "TOLERANCE") "±1%") (field (name "Comment") "Thick Film"))
      (libsource (lib "PBL - Resistors") (part "RES_100R_0603_1%"))
    )
    (comp (ref "R60")
      (value "100R")
      (footprint "RESC1608X55N")
      (description "Resistor SMD chip 100 Ohm 0.1W 1% 0603")
      (fields (field (name "TOLERANCE") "±1%") (field (name "Comment") "Thick Film"))
      (libsource (lib "PBL - Resistors") (part "RES_100R_0603_1%"))
    )
    (comp (ref "R61")
      (value "100R")
      (footprint "RESC1608X55N")
      (description "Resistor SMD chip 100 Ohm 0.1W 1% 0603")
      (fields (field (name "TOLERANCE") "±1%") (field (name "Comment") "Thick Film"))
      (libsource (lib "PBL - Resistors") (part "RES_100R_0603_1%"))
    )
    (comp (ref "R62")
      (value "1K5")
      (footprint "RESC1608X55N")
      (description "Resistor SMD chip 1.5k Ohm 0.1W 5% 0603")
      (fields (field (name "TOLERANCE") "±5%") (field (name "Comment") "Thick Film"))
      (libsource (lib "PBL - Resistors") (part "RES_1K5_0603_5%"))
    )
    (comp (ref "R63")
      (value "1K5")
      (footprint "RESC1608X55N")
      (description "Resistor SMD chip 1.5k Ohm 0.1W 5% 0603")
      (fields (field (name "TOLERANCE") "±5%") (field (name "Comment") "Thick Film"))
      (libsource (lib "PBL - Resistors") (part "RES_1K5_0603_5%"))
    )
    (comp (ref "R64")
      (value "200K")
      (footprint "RESC1608X55N")
      (description "Resistor SMD chip 200K Ohm 0.1W 5% 0603")
      (fields (field (name "TOLERANCE") "±5%") (field (name "Comment") "Thick Film"))
      (libsource (lib "") (part "RES_200K_0603_5%_1"))
    )
    (comp (ref "R65")
      (value "10K")
      (footprint "RESC1608X55N")
      (description "Resistor SMD chip 10k Ohm 0.1W 5% 0603")
      (fields (field (name "TOLERANCE") "±5%") (field (name "Comment") "Thick Film"))
      (libsource (lib "") (part "RES_10K_0603_5%_2"))
    )
    (comp (ref "R66")
      (value "10K")
      (footprint "RESC1608X55N")
      (description "Resistor SMD chip 10k Ohm 0.1W 5% 0603")
      (fields (field (name "TOLERANCE") "±5%") (field (name "Comment") "Thick Film"))
      (libsource (lib "") (part "RES_10K_0603_5%_2"))
    )
    (comp (ref "R67")
      (value "31K6")
      (footprint "RESC1608X55N")
      (description "Resistor SMD chip 31.6k Ohm 0.1W 1% 0603")
      (fields (field (name "TOLERANCE") "±1%") (field (name "Comment") "Thick Film"))
      (libsource (lib "PBL - Resistors") (part "RES_31K6_0603_1%"))
    )
    (comp (ref "R68")
      (value "31K6")
      (footprint "RESC1608X55N")
      (description "Resistor SMD chip 31.6k Ohm 0.1W 1% 0603")
      (fields (field (name "TOLERANCE") "±1%") (field (name "Comment") "Thick Film"))
      (libsource (lib "PBL - Resistors") (part "RES_31K6_0603_1%"))
    )
    (comp (ref "R69")
      (value "31K6")
      (footprint "RESC1608X55N")
      (description "Resistor SMD chip 31.6k Ohm 0.1W 1% 0603")
      (fields (field (name "TOLERANCE") "±1%") (field (name "Comment") "Thick Film"))
      (libsource (lib "PBL - Resistors") (part "RES_31K6_0603_1%"))
    )
    (comp (ref "R70")
      (value "31K6")
      (footprint "RESC1608X55N")
      (description "Resistor SMD chip 31.6k Ohm 0.1W 1% 0603")
      (fields (field (name "TOLERANCE") "±1%") (field (name "Comment") "Thick Film"))
      (libsource (lib "PBL - Resistors") (part "RES_31K6_0603_1%"))
    )
    (comp (ref "R71")
      (value "10K")
      (footprint "RESC1608X55N")
      (description "Resistor SMD chip 10k Ohm 0.1W 5% 0603")
      (fields (field (name "TOLERANCE") "±5%") (field (name "Comment") "Thick Film"))
      (libsource (lib "") (part "RES_10K_0603_5%_2"))
    )
    (comp (ref "R72")
      (value "10K")
      (footprint "RESC1608X55N")
      (description "Resistor SMD chip 10k Ohm 0.1W 5% 0603")
      (fields (field (name "TOLERANCE") "±5%") (field (name "Comment") "Thick Film"))
      (libsource (lib "") (part "RES_10K_0603_5%_2"))
    )
    (comp (ref "R73")
      (value "10K")
      (footprint "RESC1608X55N")
      (description "Resistor SMD chip 10k Ohm 0.1W 5% 0603")
      (fields (field (name "TOLERANCE") "±5%") (field (name "Comment") "Thick Film"))
      (libsource (lib "") (part "RES_10K_0603_5%_2"))
    )
    (comp (ref "R74")
      (value "10K")
      (footprint "RESC1608X55N")
      (description "Resistor SMD chip 10k Ohm 0.1W 5% 0603")
      (fields (field (name "TOLERANCE") "±5%") (field (name "Comment") "Thick Film"))
      (libsource (lib "") (part "RES_10K_0603_5%_2"))
    )
    (comp (ref "R75")
      (value "100R")
      (footprint "RESC1608X55N")
      (description "Resistor SMD chip 100 Ohm 0.1W 1% 0603")
      (fields (field (name "TOLERANCE") "±1%") (field (name "Comment") "Thick Film"))
      (libsource (lib "PBL - Resistors") (part "RES_100R_0603_1%"))
    )
    (comp (ref "R79")
      (value "1.74K")
      (footprint "RESC1608X55N")
      (description "Resistor SMD chip 1.74k Ohm 0.1W 1% 0603")
      (fields (field (name "TOLERANCE") "±1%") (field (name "Comment") "Thick Film"))
      (libsource (lib "") (part "RES_1K74_0603_1%_1"))
    )
    (comp (ref "R80")
      (value "1.74K")
      (footprint "RESC1608X55N")
      (description "Resistor SMD chip 1.74k Ohm 0.1W 1% 0603")
      (fields (field (name "TOLERANCE") "±1%") (field (name "Comment") "Thick Film"))
      (libsource (lib "") (part "RES_1K74_0603_1%_1"))
    )
    (comp (ref "R81")
      (value "1.74K")
      (footprint "RESC1608X55N")
      (description "Resistor SMD chip 1.74k Ohm 0.1W 1% 0603")
      (fields (field (name "TOLERANCE") "±1%") (field (name "Comment") "Thick Film"))
      (libsource (lib "") (part "RES_1K74_0603_1%_1"))
    )
    (comp (ref "R82")
      (value "1.74K")
      (footprint "RESC1608X55N")
      (description "Resistor SMD chip 1.74k Ohm 0.1W 1% 0603")
      (fields (field (name "TOLERANCE") "±1%") (field (name "Comment") "Thick Film"))
      (libsource (lib "") (part "RES_1K74_0603_1%_1"))
    )
    (comp (ref "R83")
      (value "1.74K")
      (footprint "RESC1608X55N")
      (description "Resistor SMD chip 1.74k Ohm 0.1W 1% 0603")
      (fields (field (name "TOLERANCE") "±1%") (field (name "Comment") "Thick Film"))
      (libsource (lib "") (part "RES_1K74_0603_1%_1"))
    )
    (comp (ref "R84")
      (value "1.74K")
      (footprint "RESC1608X55N")
      (description "Resistor SMD chip 1.74k Ohm 0.1W 1% 0603")
      (fields (field (name "TOLERANCE") "±1%") (field (name "Comment") "Thick Film"))
      (libsource (lib "") (part "RES_1K74_0603_1%_1"))
    )
    (comp (ref "R85")
      (value "1.74K")
      (footprint "RESC1608X55N")
      (description "Resistor SMD chip 1.74k Ohm 0.1W 1% 0603")
      (fields (field (name "TOLERANCE") "±1%") (field (name "Comment") "Thick Film"))
      (libsource (lib "") (part "RES_1K74_0603_1%_1"))
    )
    (comp (ref "R86")
      (value "1.74K")
      (footprint "RESC1608X55N")
      (description "Resistor SMD chip 1.74k Ohm 0.1W 1% 0603")
      (fields (field (name "TOLERANCE") "±1%") (field (name "Comment") "Thick Film"))
      (libsource (lib "") (part "RES_1K74_0603_1%_1"))
    )
    (comp (ref "R87")
      (value "1.74K")
      (footprint "RESC1608X55N")
      (description "Resistor SMD chip 1.74k Ohm 0.1W 1% 0603")
      (fields (field (name "TOLERANCE") "±1%") (field (name "Comment") "Thick Film"))
      (libsource (lib "") (part "RES_1K74_0603_1%_1"))
    )
    (comp (ref "R88")
      (value "1.74K")
      (footprint "RESC1608X55N")
      (description "Resistor SMD chip 1.74k Ohm 0.1W 1% 0603")
      (fields (field (name "TOLERANCE") "±1%") (field (name "Comment") "Thick Film"))
      (libsource (lib "") (part "RES_1K74_0603_1%_1"))
    )
    (comp (ref "R89")
      (value "1.74K")
      (footprint "RESC1608X55N")
      (description "Resistor SMD chip 1.74k Ohm 0.1W 1% 0603")
      (fields (field (name "TOLERANCE") "±1%") (field (name "Comment") "Thick Film"))
      (libsource (lib "") (part "RES_1K74_0603_1%_1"))
    )
    (comp (ref "R90")
      (value "1.74K")
      (footprint "RESC1608X55N")
      (description "Resistor SMD chip 1.74k Ohm 0.1W 1% 0603")
      (fields (field (name "TOLERANCE") "±1%") (field (name "Comment") "Thick Film"))
      (libsource (lib "") (part "RES_1K74_0603_1%_1"))
    )
    (comp (ref "R91")
      (value "1.74K")
      (footprint "RESC1608X55N")
      (description "Resistor SMD chip 1.74k Ohm 0.1W 1% 0603")
      (fields (field (name "TOLERANCE") "±1%") (field (name "Comment") "Thick Film"))
      (libsource (lib "") (part "RES_1K74_0603_1%_1"))
    )
    (comp (ref "R92")
      (value "1.74K")
      (footprint "RESC1608X55N")
      (description "Resistor SMD chip 1.74k Ohm 0.1W 1% 0603")
      (fields (field (name "TOLERANCE") "±1%") (field (name "Comment") "Thick Film"))
      (libsource (lib "") (part "RES_1K74_0603_1%_1"))
    )
    (comp (ref "R93")
      (value "1.74K")
      (footprint "RESC1608X55N")
      (description "Resistor SMD chip 1.74k Ohm 0.1W 1% 0603")
      (fields (field (name "TOLERANCE") "±1%") (field (name "Comment") "Thick Film"))
      (libsource (lib "") (part "RES_1K74_0603_1%_1"))
    )
    (comp (ref "R94")
      (value "1.74K")
      (footprint "RESC1608X55N")
      (description "Resistor SMD chip 1.74k Ohm 0.1W 1% 0603")
      (fields (field (name "TOLERANCE") "±1%") (field (name "Comment") "Thick Film"))
      (libsource (lib "") (part "RES_1K74_0603_1%_1"))
    )
    (comp (ref "R95")
      (value "1.74K")
      (footprint "RESC1608X55N")
      (description "Resistor SMD chip 1.74k Ohm 0.1W 1% 0603")
      (fields (field (name "TOLERANCE") "±1%") (field (name "Comment") "Thick Film"))
      (libsource (lib "PBL - Resistors") (part "RES_1K74_0603_1%"))
    )
    (comp (ref "R96")
      (value "1.74K")
      (footprint "RESC1608X55N")
      (description "Resistor SMD chip 1.74k Ohm 0.1W 1% 0603")
      (fields (field (name "TOLERANCE") "±1%") (field (name "Comment") "Thick Film"))
      (libsource (lib "PBL - Resistors") (part "RES_1K74_0603_1%"))
    )
    (comp (ref "R97")
      (value "1.74K")
      (footprint "RESC1608X55N")
      (description "Resistor SMD chip 1.74k Ohm 0.1W 1% 0603")
      (fields (field (name "TOLERANCE") "±1%") (field (name "Comment") "Thick Film"))
      (libsource (lib "PBL - Resistors") (part "RES_1K74_0603_1%"))
    )
    (comp (ref "R98")
      (value "1.74K")
      (footprint "RESC1608X55N")
      (description "Resistor SMD chip 1.74k Ohm 0.1W 1% 0603")
      (fields (field (name "TOLERANCE") "±1%") (field (name "Comment") "Thick Film"))
      (libsource (lib "PBL - Resistors") (part "RES_1K74_0603_1%"))
    )
    (comp (ref "R99")
      (value "1.74K")
      (footprint "RESC1608X55N")
      (description "Resistor SMD chip 1.74k Ohm 0.1W 1% 0603")
      (fields (field (name "TOLERANCE") "±1%") (field (name "Comment") "Thick Film"))
      (libsource (lib "PBL - Resistors") (part "RES_1K74_0603_1%"))
    )
    (comp (ref "R100")
      (value "1.74K")
      (footprint "RESC1608X55N")
      (description "Resistor SMD chip 1.74k Ohm 0.1W 1% 0603")
      (fields (field (name "TOLERANCE") "±1%") (field (name "Comment") "Thick Film"))
      (libsource (lib "PBL - Resistors") (part "RES_1K74_0603_1%"))
    )
    (comp (ref "R101")
      (value "1.74K")
      (footprint "RESC1608X55N")
      (description "Resistor SMD chip 1.74k Ohm 0.1W 1% 0603")
      (fields (field (name "TOLERANCE") "±1%") (field (name "Comment") "Thick Film"))
      (libsource (lib "PBL - Resistors") (part "RES_1K74_0603_1%"))
    )
    (comp (ref "R102")
      (value "1.74K")
      (footprint "RESC1608X55N")
      (description "Resistor SMD chip 1.74k Ohm 0.1W 1% 0603")
      (fields (field (name "TOLERANCE") "±1%") (field (name "Comment") "Thick Film"))
      (libsource (lib "PBL - Resistors") (part "RES_1K74_0603_1%"))
    )
    (comp (ref "R103")
      (value "1.74K")
      (footprint "RESC1608X55N")
      (description "Resistor SMD chip 1.74k Ohm 0.1W 1% 0603")
      (fields (field (name "TOLERANCE") "±1%") (field (name "Comment") "Thick Film"))
      (libsource (lib "PBL - Resistors") (part "RES_1K74_0603_1%"))
    )
    (comp (ref "R104")
      (value "1.74K")
      (footprint "RESC1608X55N")
      (description "Resistor SMD chip 1.74k Ohm 0.1W 1% 0603")
      (fields (field (name "TOLERANCE") "±1%") (field (name "Comment") "Thick Film"))
      (libsource (lib "PBL - Resistors") (part "RES_1K74_0603_1%"))
    )
    (comp (ref "R105")
      (value "1.74K")
      (footprint "RESC1608X55N")
      (description "Resistor SMD chip 1.74k Ohm 0.1W 1% 0603")
      (fields (field (name "TOLERANCE") "±1%") (field (name "Comment") "Thick Film"))
      (libsource (lib "PBL - Resistors") (part "RES_1K74_0603_1%"))
    )
    (comp (ref "R106")
      (value "1.74K")
      (footprint "RESC1608X55N")
      (description "Resistor SMD chip 1.74k Ohm 0.1W 1% 0603")
      (fields (field (name "TOLERANCE") "±1%") (field (name "Comment") "Thick Film"))
      (libsource (lib "PBL - Resistors") (part "RES_1K74_0603_1%"))
    )
    (comp (ref "R107")
      (value "1.74K")
      (footprint "RESC1608X55N")
      (description "Resistor SMD chip 1.74k Ohm 0.1W 1% 0603")
      (fields (field (name "TOLERANCE") "±1%") (field (name "Comment") "Thick Film"))
      (libsource (lib "PBL - Resistors") (part "RES_1K74_0603_1%"))
    )
    (comp (ref "R108")
      (value "1.74K")
      (footprint "RESC1608X55N")
      (description "Resistor SMD chip 1.74k Ohm 0.1W 1% 0603")
      (fields (field (name "TOLERANCE") "±1%") (field (name "Comment") "Thick Film"))
      (libsource (lib "PBL - Resistors") (part "RES_1K74_0603_1%"))
    )
    (comp (ref "R109")
      (value "1.74K")
      (footprint "RESC1608X55N")
      (description "Resistor SMD chip 1.74k Ohm 0.1W 1% 0603")
      (fields (field (name "TOLERANCE") "±1%") (field (name "Comment") "Thick Film"))
      (libsource (lib "PBL - Resistors") (part "RES_1K74_0603_1%"))
    )
    (comp (ref "R110")
      (value "1.74K")
      (footprint "RESC1608X55N")
      (description "Resistor SMD chip 1.74k Ohm 0.1W 1% 0603")
      (fields (field (name "TOLERANCE") "±1%") (field (name "Comment") "Thick Film"))
      (libsource (lib "PBL - Resistors") (part "RES_1K74_0603_1%"))
    )
    (comp (ref "R111")
      (value "1.74K")
      (footprint "RESC1608X55N")
      (description "Resistor SMD chip 1.74k Ohm 0.1W 1% 0603")
      (fields (field (name "TOLERANCE") "±1%") (field (name "Comment") "Thick Film"))
      (libsource (lib "PBL - Resistors") (part "RES_1K74_0603_1%"))
    )
    (comp (ref "R112")
      (value "1.74K")
      (footprint "RESC1608X55N")
      (description "Resistor SMD chip 1.74k Ohm 0.1W 1% 0603")
      (fields (field (name "TOLERANCE") "±1%") (field (name "Comment") "Thick Film"))
      (libsource (lib "PBL - Resistors") (part "RES_1K74_0603_1%"))
    )
    (comp (ref "R113")
      (value "1.74K")
      (footprint "RESC1608X55N")
      (description "Resistor SMD chip 1.74k Ohm 0.1W 1% 0603")
      (fields (field (name "TOLERANCE") "±1%") (field (name "Comment") "Thick Film"))
      (libsource (lib "PBL - Resistors") (part "RES_1K74_0603_1%"))
    )
    (comp (ref "R114")
      (value "1.74K")
      (footprint "RESC1608X55N")
      (description "Resistor SMD chip 1.74k Ohm 0.1W 1% 0603")
      (fields (field (name "TOLERANCE") "±1%") (field (name "Comment") "Thick Film"))
      (libsource (lib "PBL - Resistors") (part "RES_1K74_0603_1%"))
    )
    (comp (ref "R115")
      (value "1.74K")
      (footprint "RESC1608X55N")
      (description "Resistor SMD chip 1.74k Ohm 0.1W 1% 0603")
      (fields (field (name "TOLERANCE") "±1%") (field (name "Comment") "Thick Film"))
      (libsource (lib "PBL - Resistors") (part "RES_1K74_0603_1%"))
    )
    (comp (ref "R116")
      (value "1.74K")
      (footprint "RESC1608X55N")
      (description "Resistor SMD chip 1.74k Ohm 0.1W 1% 0603")
      (fields (field (name "TOLERANCE") "±1%") (field (name "Comment") "Thick Film"))
      (libsource (lib "PBL - Resistors") (part "RES_1K74_0603_1%"))
    )
    (comp (ref "R117")
      (value "1.74K")
      (footprint "RESC1608X55N")
      (description "Resistor SMD chip 1.74k Ohm 0.1W 1% 0603")
      (fields (field (name "TOLERANCE") "±1%") (field (name "Comment") "Thick Film"))
      (libsource (lib "PBL - Resistors") (part "RES_1K74_0603_1%"))
    )
    (comp (ref "R118")
      (value "1.74K")
      (footprint "RESC1608X55N")
      (description "Resistor SMD chip 1.74k Ohm 0.1W 1% 0603")
      (fields (field (name "TOLERANCE") "±1%") (field (name "Comment") "Thick Film"))
      (libsource (lib "PBL - Resistors") (part "RES_1K74_0603_1%"))
    )
    (comp (ref "R119")
      (value "1.74K")
      (footprint "RESC1608X55N")
      (description "Resistor SMD chip 1.74k Ohm 0.1W 1% 0603")
      (fields (field (name "TOLERANCE") "±1%") (field (name "Comment") "Thick Film"))
      (libsource (lib "PBL - Resistors") (part "RES_1K74_0603_1%"))
    )
    (comp (ref "R120")
      (value "1.74K")
      (footprint "RESC1608X55N")
      (description "Resistor SMD chip 1.74k Ohm 0.1W 1% 0603")
      (fields (field (name "TOLERANCE") "±1%") (field (name "Comment") "Thick Film"))
      (libsource (lib "PBL - Resistors") (part "RES_1K74_0603_1%"))
    )
    (comp (ref "S0")
      (value "FSM4JSMA")
      (footprint "TACT_6mmx6mm")
      (description "TACT_SWITCH 6x6")
      (fields (field (name "FUNCTION") "On/Off") (field (name "SUPPLIER PART NUMBER 1") "450-1129-ND"))
      (libsource (lib "PBL - Switches") (part "TACT_SWITCH 6x6"))
    )
    (comp (ref "S1")
      (value "FSM4JSMA")
      (footprint "TACT_6mmx6mm")
      (description "TACT_SWITCH 6x6")
      (fields (field (name "FUNCTION") "On/Off") (field (name "SUPPLIER PART NUMBER 1") "450-1129-ND"))
      (libsource (lib "PBL - Switches") (part "TACT_SWITCH 6x6"))
    )
    (comp (ref "S2")
      (value "FSM4JSMA")
      (footprint "TACT_6mmx6mm")
      (description "TACT_SWITCH 6x6")
      (fields (field (name "FUNCTION") "On/Off") (field (name "SUPPLIER PART NUMBER 1") "450-1129-ND"))
      (libsource (lib "PBL - Switches") (part "TACT_SWITCH 6x6"))
    )
    (comp (ref "S3")
      (value "FSM4JSMA")
      (footprint "TACT_6mmx6mm")
      (description "TACT_SWITCH 6x6")
      (fields (field (name "FUNCTION") "On/Off") (field (name "SUPPLIER PART NUMBER 1") "450-1129-ND"))
      (libsource (lib "PBL - Switches") (part "TACT_SWITCH 6x6"))
    )
    (comp (ref "S4")
      (value "FSM4JSMA")
      (footprint "TACT_6mmx6mm")
      (description "TACT_SWITCH 6x6")
      (fields (field (name "FUNCTION") "On/Off") (field (name "SUPPLIER PART NUMBER 1") "450-1129-ND"))
      (libsource (lib "PBL - Switches") (part "TACT_SWITCH 6x6"))
    )
    (comp (ref "S5")
      (value "FSM4JSMA")
      (footprint "TACT_6mmx6mm")
      (description "TACT_SWITCH 6x6")
      (fields (field (name "FUNCTION") "On/Off") (field (name "SUPPLIER PART NUMBER 1") "450-1129-ND"))
      (libsource (lib "PBL - Switches") (part "TACT_SWITCH 6x6"))
    )
    (comp (ref "S6")
      (value "FSM4JSMA")
      (footprint "TACT_6mmx6mm")
      (description "TACT_SWITCH 6x6")
      (fields (field (name "FUNCTION") "On/Off") (field (name "SUPPLIER PART NUMBER 1") "450-1129-ND"))
      (libsource (lib "PBL - Switches") (part "TACT_SWITCH 6x6"))
    )
    (comp (ref "S7")
      (value "FSM4JSMA")
      (footprint "TACT_6mmx6mm")
      (description "TACT_SWITCH 6x6")
      (fields (field (name "FUNCTION") "On/Off") (field (name "SUPPLIER PART NUMBER 1") "450-1129-ND"))
      (libsource (lib "PBL - Switches") (part "TACT_SWITCH 6x6"))
    )
    (comp (ref "SCL")
      (value "Jumper")
      (footprint "JUMP1")
      (description "SMD jumper")
      (libsource (lib "PBL - Pads and Jumpers") (part "JUMP1"))
    )
    (comp (ref "SCL_R")
      (value "4K7")
      (footprint "RESC1608X55N")
      (description "Resistor SMD chip 4.7k Ohm 0.1W 5% 0603")
      (fields (field (name "TOLERANCE") "±5%") (field (name "Comment") "Thick Film"))
      (libsource (lib "PBL - Resistors") (part "RES_4K7_0603_5%"))
    )
    (comp (ref "SDA")
      (value "Jumper")
      (footprint "JUMP1")
      (description "SMD jumper")
      (libsource (lib "PBL - Pads and Jumpers") (part "JUMP1"))
    )
    (comp (ref "SDA_R")
      (value "4K7")
      (footprint "RESC1608X55N")
      (description "Resistor SMD chip 4.7k Ohm 0.1W 5% 0603")
      (fields (field (name "TOLERANCE") "±5%") (field (name "Comment") "Thick Film"))
      (libsource (lib "PBL - Resistors") (part "RES_4K7_0603_5%"))
    )
    (comp (ref "SRV0")
      (value "JST_PH_B3B")
      (footprint "JST_PH_3_B3B")
      (description "2mm Pitch")
      (libsource (lib "PBL - Connectors") (part "JST_PH_B3B"))
    )
    (comp (ref "SRV1")
      (value "JST_PH_B3B")
      (footprint "JST_PH_3_B3B")
      (description "2mm Pitch")
      (libsource (lib "PBL - Connectors") (part "JST_PH_B3B"))
    )
    (comp (ref "SRV2")
      (value "JST_PH_B3B")
      (footprint "JST_PH_3_B3B")
      (description "2mm Pitch")
      (libsource (lib "PBL - Connectors") (part "JST_PH_B3B"))
    )
    (comp (ref "SRV3")
      (value "JST_PH_B3B")
      (footprint "JST_PH_3_B3B")
      (description "2mm Pitch")
      (libsource (lib "PBL - Connectors") (part "JST_PH_B3B"))
    )
    (comp (ref "SRV4")
      (value "JST_PH_B3B")
      (footprint "JST_PH_3_B3B")
      (description "2mm Pitch")
      (libsource (lib "PBL - Connectors") (part "JST_PH_B3B"))
    )
    (comp (ref "SW1")
      (value "JST_PH_B2B")
      (footprint "JST_PH_2_B2B")
      (description "2mm Pitch")
      (libsource (lib "PBL - Connectors") (part "JST_PH_B2B"))
    )
    (comp (ref "SW2")
      (value "JST_PH_B2B")
      (footprint "JST_PH_2_B2B")
      (description "2mm Pitch")
      (libsource (lib "PBL - Connectors") (part "JST_PH_B2B"))
    )
    (comp (ref "SW3")
      (value "JST_PH_B2B")
      (footprint "JST_PH_2_B2B")
      (description "2mm Pitch")
      (libsource (lib "PBL - Connectors") (part "JST_PH_B2B"))
    )
    (comp (ref "SW4")
      (value "JST_PH_B2B")
      (footprint "JST_PH_2_B2B")
      (description "2mm Pitch")
      (libsource (lib "PBL - Connectors") (part "JST_PH_B2B"))
    )
    (comp (ref "U2")
      (value "Arduino Pro Mini")
      (footprint "Arduino Pro Mini")
      (fields (field (name "SUPPLIER PART NUMBER 1") "1568-1054-ND"))
      (libsource (lib "RyanMasterLib") (part "Arduino Pro Mini"))
    )
    (comp (ref "U3")
      (value "PCA9554")
      (footprint "TSSOP65P640X120-16N")
      (description "IO EXPANDER PUSH PULL WEAK PULLUP")
      (fields (field (name "SUPPLIER PART NUMBER 1") "568-1055-1-ND"))
      (libsource (lib "IC Digital") (part "PCA9554"))
    )
    (comp (ref "U4")
      (value "PA9685")
      (footprint "TSSOP28")
      (description "LED Driver IC 16 Output Linear PWM Dimming 25mA 28-TSSOP")
      (fields (field (name "SUPPLIER PART NUMBER 1") "568-8366-5-ND"))
      (libsource (lib "IC Digital") (part "PCA9685"))
    )
    (comp (ref "U7")
      (value "NVT2008")
      (footprint "TSSOP65P640X120-20N")
      (description "IC TRANSLATOR BIDIR VOLT 20TSSOP")
      (fields (field (name "SUPPLIER PART NUMBER 1") "568-5297-1-ND"))
      (libsource (lib "") (part "IC_VLEVEL_TRANSLATOR_NVT2008_1"))
    )
    (comp (ref "U8")
      (value "NVT2008")
      (footprint "TSSOP65P640X120-20N")
      (description "IC TRANSLATOR BIDIR VOLT 20TSSOP")
      (fields (field (name "SUPPLIER PART NUMBER 1") "568-5297-1-ND"))
      (libsource (lib "") (part "IC_VLEVEL_TRANSLATOR_NVT2008_1"))
    )
    (comp (ref "U9")
      (value "NVT2008")
      (footprint "TSSOP65P640X120-20N")
      (description "IC TRANSLATOR BIDIR VOLT 20TSSOP")
      (fields (field (name "SUPPLIER PART NUMBER 1") "568-5297-1-ND"))
      (libsource (lib "PBL - Integrated Circuits") (part "IC_VLEVEL_TRANSLATOR_NVT2008"))
    )
    (comp (ref "U10")
      (value "ADS7828")
      (footprint "TSSOP65P640X120-16N")
      (description "12-Bit, 8-Channel Sampling ANALOG-TO-DIGITAL CONVERTER with I2C™ Interface")
      (fields (field (name "SUPPLIER PART NUMBER 1") "296-38856-1-ND"))
      (libsource (lib "IC Digital") (part "ADS7828"))
    )
    (comp (ref "U11")
      (value "BNO_055")
      (footprint "BNO-055")
      (description "9-axis motion sensor with hardware fusion")
      (libsource (lib "RyanMasterLib") (part "BNO_055"))
    )
  )
  (nets
    (net (code "1") (name "/3.3V") (class "Default")
      (node (ref "A0_AD") (pin "1") (pintype "passive"))
      (node (ref "A0_IO") (pin "2") (pintype "passive"))
      (node (ref "A0_PWM") (pin "2") (pintype "passive"))
      (node (ref "A1_AD") (pin "1") (pintype "passive"))
      (node (ref "A1_IO") (pin "2") (pintype "passive"))
      (node (ref "A1_PWM") (pin "2") (pintype "passive"))
      (node (ref "A2_IO") (pin "2") (pintype "passive"))
      (node (ref "A2_PWM") (pin "2") (pintype "passive"))
      (node (ref "A3_PWM") (pin "2") (pintype "passive"))
      (node (ref "A4_PWM") (pin "2") (pintype "passive"))
      (node (ref "A5_PWM") (pin "2") (pintype "passive"))
      (node (ref "AD1") (pin "1") (pinfunction "1_1") (pintype "passive"))
      (node (ref "AD2") (pin "1") (pinfunction "1_1") (pintype "passive"))
      (node (ref "AD3") (pin "1") (pinfunction "1_1") (pintype "passive"))
      (node (ref "AD4") (pin "1") (pinfunction "1_1") (pintype "passive"))
      (node (ref "C15") (pin "1") (pintype "passive"))
      (node (ref "C16") (pin "1") (pintype "passive"))
      (node (ref "C17") (pin "1") (pintype "passive"))
      (node (ref "C20") (pin "2") (pintype "passive"))
      (node (ref "C21") (pin "2") (pintype "passive"))
      (node (ref "C22") (pin "2") (pintype "passive"))
      (node (ref "C31") (pin "1") (pintype "passive"))
      (node (ref "C32") (pin "1") (pintype "passive"))
      (node (ref "C33") (pin "1") (pintype "passive"))
      (node (ref "C45") (pin "1") (pintype "passive"))
      (node (ref "C46") (pin "1") (pintype "passive"))
      (node (ref "C47") (pin "1") (pintype "passive"))
      (node (ref "C56") (pin "2") (pintype "passive"))
      (node (ref "C58") (pin "1") (pintype "passive"))
      (node (ref "C60") (pin "1") (pintype "passive"))
      (node (ref "C61") (pin "1") (pintype "passive"))
      (node (ref "C62") (pin "1") (pintype "passive"))
      (node (ref "C63") (pin "1") (pintype "passive"))
      (node (ref "C64") (pin "1") (pintype "passive"))
      (node (ref "D2") (pin "2") (pinfunction "2_2") (pintype "passive"))
      (node (ref "D3") (pin "2") (pinfunction "2_2") (pintype "passive"))
      (node (ref "D4") (pin "2") (pinfunction "2_2") (pintype "passive"))
      (node (ref "D5") (pin "2") (pinfunction "2_2") (pintype "passive"))
      (node (ref "D6") (pin "2") (pinfunction "2_2") (pintype "passive"))
      (node (ref "D7") (pin "2") (pinfunction "2_2") (pintype "passive"))
      (node (ref "D8") (pin "2") (pinfunction "2_2") (pintype "passive"))
      (node (ref "D9") (pin "2") (pinfunction "2_2") (pintype "passive"))
      (node (ref "OE_PWM") (pin "2") (pintype "passive"))
      (node (ref "R100") (pin "1") (pinfunction "1_1") (pintype "passive"))
      (node (ref "R103") (pin "1") (pinfunction "1_1") (pintype "passive"))
      (node (ref "R104") (pin "1") (pinfunction "1_1") (pintype "passive"))
      (node (ref "R107") (pin "1") (pinfunction "1_1") (pintype "passive"))
      (node (ref "R108") (pin "1") (pinfunction "1_1") (pintype "passive"))
      (node (ref "R111") (pin "1") (pinfunction "1_1") (pintype "passive"))
      (node (ref "R113") (pin "1") (pinfunction "1_1") (pintype "passive"))
      (node (ref "R115") (pin "1") (pinfunction "1_1") (pintype "passive"))
      (node (ref "R117") (pin "1") (pinfunction "1_1") (pintype "passive"))
      (node (ref "R119") (pin "1") (pinfunction "1_1") (pintype "passive"))
      (node (ref "R14") (pin "1") (pinfunction "1_1") (pintype "passive"))
      (node (ref "R18") (pin "1") (pinfunction "1_1") (pintype "passive"))
      (node (ref "R28") (pin "1") (pinfunction "1_1") (pintype "passive"))
      (node (ref "R32") (pin "1") (pinfunction "1_1") (pintype "passive"))
      (node (ref "R40") (pin "1") (pinfunction "1_1") (pintype "passive"))
      (node (ref "R44") (pin "1") (pinfunction "1_1") (pintype "passive"))
      (node (ref "R47") (pin "1") (pinfunction "1_1") (pintype "passive"))
      (node (ref "R51") (pin "1") (pinfunction "1_1") (pintype "passive"))
      (node (ref "R79") (pin "1") (pinfunction "1_1") (pintype "passive"))
      (node (ref "R80") (pin "1") (pinfunction "1_1") (pintype "passive"))
      (node (ref "R83") (pin "1") (pinfunction "1_1") (pintype "passive"))
      (node (ref "R84") (pin "1") (pinfunction "1_1") (pintype "passive"))
      (node (ref "R87") (pin "1") (pinfunction "1_1") (pintype "passive"))
      (node (ref "R88") (pin "1") (pinfunction "1_1") (pintype "passive"))
      (node (ref "R91") (pin "1") (pinfunction "1_1") (pintype "passive"))
      (node (ref "R92") (pin "1") (pinfunction "1_1") (pintype "passive"))
      (node (ref "R95") (pin "1") (pinfunction "1_1") (pintype "passive"))
      (node (ref "R96") (pin "1") (pinfunction "1_1") (pintype "passive"))
      (node (ref "R99") (pin "1") (pinfunction "1_1") (pintype "passive"))
      (node (ref "SCL_R") (pin "1") (pinfunction "1_1") (pintype "passive"))
      (node (ref "SDA_R") (pin "1") (pinfunction "1_1") (pintype "passive"))
      (node (ref "U10") (pin "10") (pinfunction "REF_IN/OUT_10") (pintype "passive"))
      (node (ref "U10") (pin "16") (pinfunction "VDD_16") (pintype "passive"))
      (node (ref "U11") (pin "2") (pinfunction "VDD_2") (pintype "passive"))
      (node (ref "U2") (pin "VCC") (pinfunction "VCC_VCC") (pintype "passive"))
      (node (ref "U3") (pin "16") (pinfunction "VCC_16") (pintype "passive"))
      (node (ref "U4") (pin "28") (pinfunction "Vdd_28") (pintype "passive"))
      (node (ref "U7") (pin "2") (pinfunction "VREFA_2") (pintype "passive"))
      (node (ref "U8") (pin "2") (pinfunction "VREFA_2") (pintype "passive"))
      (node (ref "U9") (pin "2") (pinfunction "VREFA_2") (pintype "passive"))
    )
    (net (code "2") (name "/5V") (class "Default")
      (node (ref "C23") (pin "+") (pinfunction "+_+") (pintype "passive"))
      (node (ref "C24") (pin "+") (pinfunction "+_+") (pintype "passive"))
      (node (ref "C25") (pin "+") (pinfunction "+_+") (pintype "passive"))
      (node (ref "C26") (pin "+") (pinfunction "+_+") (pintype "passive"))
      (node (ref "C42") (pin "1") (pintype "passive"))
      (node (ref "C48") (pin "1") (pintype "passive"))
      (node (ref "C50") (pin "1") (pintype "passive"))
      (node (ref "DS1") (pin "4") (pinfunction "4_4") (pintype "passive"))
      (node (ref "DS2") (pin "4") (pinfunction "4_4") (pintype "passive"))
      (node (ref "DS3") (pin "4") (pinfunction "4_4") (pintype "passive"))
      (node (ref "DS4") (pin "4") (pinfunction "4_4") (pintype "passive"))
      (node (ref "J8") (pin "2") (pinfunction "D_GND_2") (pintype "passive"))
      (node (ref "J8") (pin "4") (pinfunction "D_GND_4") (pintype "passive"))
      (node (ref "MTR1") (pin "2") (pintype "passive"))
      (node (ref "MTR2") (pin "2") (pintype "passive"))
      (node (ref "MTR3") (pin "2") (pintype "passive"))
      (node (ref "MTR4") (pin "2") (pintype "passive"))
      (node (ref "R101") (pin "1") (pinfunction "1_1") (pintype "passive"))
      (node (ref "R102") (pin "1") (pinfunction "1_1") (pintype "passive"))
      (node (ref "R105") (pin "1") (pinfunction "1_1") (pintype "passive"))
      (node (ref "R106") (pin "1") (pinfunction "1_1") (pintype "passive"))
      (node (ref "R109") (pin "1") (pinfunction "1_1") (pintype "passive"))
      (node (ref "R110") (pin "1") (pinfunction "1_1") (pintype "passive"))
      (node (ref "R112") (pin "1") (pinfunction "1_1") (pintype "passive"))
      (node (ref "R114") (pin "1") (pinfunction "1_1") (pintype "passive"))
      (node (ref "R116") (pin "1") (pinfunction "1_1") (pintype "passive"))
      (node (ref "R118") (pin "1") (pinfunction "1_1") (pintype "passive"))
      (node (ref "R120") (pin "1") (pinfunction "1_1") (pintype "passive"))
      (node (ref "R50") (pin "2") (pinfunction "2_2") (pintype "passive"))
      (node (ref "R64") (pin "2") (pinfunction "2_2") (pintype "passive"))
      (node (ref "R81") (pin "1") (pinfunction "1_1") (pintype "passive"))
      (node (ref "R82") (pin "1") (pinfunction "1_1") (pintype "passive"))
      (node (ref "R85") (pin "1") (pinfunction "1_1") (pintype "passive"))
      (node (ref "R86") (pin "1") (pinfunction "1_1") (pintype "passive"))
      (node (ref "R89") (pin "1") (pinfunction "1_1") (pintype "passive"))
      (node (ref "R9") (pin "2") (pinfunction "2_2") (pintype "passive"))
      (node (ref "R90") (pin "1") (pinfunction "1_1") (pintype "passive"))
      (node (ref "R93") (pin "1") (pinfunction "1_1") (pintype "passive"))
      (node (ref "R94") (pin "1") (pinfunction "1_1") (pintype "passive"))
      (node (ref "R97") (pin "1") (pinfunction "1_1") (pintype "passive"))
      (node (ref "R98") (pin "1") (pinfunction "1_1") (pintype "passive"))
      (node (ref "SRV0") (pin "3") (pinfunction "3_3") (pintype "passive"))
      (node (ref "SRV1") (pin "3") (pinfunction "3_3") (pintype "passive"))
      (node (ref "SRV2") (pin "3") (pinfunction "3_3") (pintype "passive"))
      (node (ref "SRV3") (pin "3") (pinfunction "3_3") (pintype "passive"))
      (node (ref "SRV4") (pin "3") (pinfunction "3_3") (pintype "passive"))
      (node (ref "SW1") (pin "2") (pinfunction "2_2") (pintype "passive"))
      (node (ref "SW2") (pin "2") (pinfunction "2_2") (pintype "passive"))
      (node (ref "SW3") (pin "2") (pinfunction "2_2") (pintype "passive"))
      (node (ref "SW4") (pin "2") (pinfunction "2_2") (pintype "passive"))
    )
    (net (code "3") (name "/AD_CH0") (class "Default")
      (node (ref "AD1") (pin "2") (pinfunction "2_2") (pintype "passive"))
      (node (ref "R67") (pin "1") (pinfunction "1_1") (pintype "passive"))
    )
    (net (code "4") (name "/AD_CH1") (class "Default")
      (node (ref "AD2") (pin "2") (pinfunction "2_2") (pintype "passive"))
      (node (ref "R68") (pin "1") (pinfunction "1_1") (pintype "passive"))
    )
    (net (code "5") (name "/AD_CH2") (class "Default")
      (node (ref "AD3") (pin "2") (pinfunction "2_2") (pintype "passive"))
      (node (ref "R69") (pin "1") (pinfunction "1_1") (pintype "passive"))
    )
    (net (code "6") (name "/AD_CH3") (class "Default")
      (node (ref "AD4") (pin "2") (pinfunction "2_2") (pintype "passive"))
      (node (ref "R70") (pin "1") (pinfunction "1_1") (pintype "passive"))
    )
    (net (code "8") (name "/AIOUT1") (class "Default")
      (node (ref "R10") (pin "2") (pinfunction "2_2") (pintype "passive"))
    )
    (net (code "9") (name "/AIOUT2") (class "Default")
      (node (ref "R13") (pin "2") (pinfunction "2_2") (pintype "passive"))
    )
    (net (code "10") (name "/AIOUT3") (class "Default")
      (node (ref "R62") (pin "2") (pinfunction "2_2") (pintype "passive"))
    )
    (net (code "11") (name "/AIOUT4") (class "Default")
      (node (ref "R63") (pin "2") (pinfunction "2_2") (pintype "passive"))
    )
    (net (code "13") (name "/A_ENC1") (class "Default")
      (node (ref "R80") (pin "2") (pinfunction "2_2") (pintype "passive"))
      (node (ref "U2") (pin "A1") (pinfunction "A1/D15_A1") (pintype "passive"))
      (node (ref "U9") (pin "10") (pinfunction "A8_10") (pintype "passive"))
    )
    (net (code "14") (name "/A_ENC2") (class "Default")
      (node (ref "R88") (pin "2") (pinfunction "2_2") (pintype "passive"))
      (node (ref "U2") (pin "13") (pinfunction "D13_13") (pintype "passive"))
      (node (ref "U9") (pin "8") (pinfunction "A6_8") (pintype "passive"))
    )
    (net (code "15") (name "/A_ENC3") (class "Default")
      (node (ref "R79") (pin "2") (pinfunction "2_2") (pintype "passive"))
      (node (ref "U2") (pin "11") (pinfunction "D11_11") (pintype "passive"))
      (node (ref "U9") (pin "6") (pinfunction "A4_6") (pintype "passive"))
    )
    (net (code "16") (name "/A_ENC4") (class "Default")
      (node (ref "R87") (pin "2") (pinfunction "2_2") (pintype "passive"))
      (node (ref "U2") (pin "2") (pinfunction "D2_2") (pintype "passive"))
      (node (ref "U9") (pin "4") (pinfunction "A2_4") (pintype "passive"))
    )
    (net (code "19") (name "/A_OUT1") (class "Default")
      (node (ref "MTR1") (pin "1") (pintype "passive"))
      (node (ref "MTR1") (pin "3") (pintype "passive"))
    )
    (net (code "20") (name "/A_OUT2") (class "Default")
      (node (ref "MTR2") (pin "1") (pintype "passive"))
      (node (ref "MTR2") (pin "3") (pintype "passive"))
    )
    (net (code "21") (name "/A_OUT3") (class "Default")
      (node (ref "MTR3") (pin "1") (pintype "passive"))
      (node (ref "MTR3") (pin "3") (pintype "passive"))
    )
    (net (code "22") (name "/A_OUT4") (class "Default")
      (node (ref "MTR4") (pin "1") (pintype "passive"))
      (node (ref "MTR4") (pin "3") (pintype "passive"))
    )
    (net (code "24") (name "/B_ENC1") (class "Default")
      (node (ref "R84") (pin "2") (pinfunction "2_2") (pintype "passive"))
      (node (ref "U2") (pin "A0") (pinfunction "A0/D14_A0") (pintype "passive"))
      (node (ref "U9") (pin "9") (pinfunction "A7_9") (pintype "passive"))
    )
    (net (code "25") (name "/B_ENC2") (class "Default")
      (node (ref "R91") (pin "2") (pinfunction "2_2") (pintype "passive"))
      (node (ref "U2") (pin "12") (pinfunction "D12_12") (pintype "passive"))
      (node (ref "U9") (pin "7") (pinfunction "A5_7") (pintype "passive"))
    )
    (net (code "26") (name "/B_ENC3") (class "Default")
      (node (ref "R83") (pin "2") (pinfunction "2_2") (pintype "passive"))
      (node (ref "U2") (pin "10") (pinfunction "D10_10") (pintype "passive"))
      (node (ref "U9") (pin "5") (pinfunction "A3_5") (pintype "passive"))
    )
    (net (code "27") (name "/B_ENC4") (class "Default")
      (node (ref "R92") (pin "2") (pinfunction "2_2") (pintype "passive"))
      (node (ref "U2") (pin "4") (pinfunction "D4_4") (pintype "passive"))
      (node (ref "U9") (pin "3") (pinfunction "A1_3") (pintype "passive"))
    )
    (net (code "30") (name "/B_OUT1") (class "Default")
      (node (ref "MTR1") (pin "5") (pintype "passive"))
      (node (ref "MTR1") (pin "7") (pintype "passive"))
    )
    (net (code "31") (name "/B_OUT2") (class "Default")
      (node (ref "MTR2") (pin "5") (pintype "passive"))
      (node (ref "MTR2") (pin "7") (pintype "passive"))
    )
    (net (code "32") (name "/B_OUT3") (class "Default")
      (node (ref "MTR3") (pin "5") (pintype "passive"))
      (node (ref "MTR3") (pin "7") (pintype "passive"))
    )
    (net (code "33") (name "/B_OUT4") (class "Default")
      (node (ref "MTR4") (pin "5") (pintype "passive"))
      (node (ref "MTR4") (pin "7") (pintype "passive"))
    )
    (net (code "35") (name "/ECHO_A_1") (class "Default")
      (node (ref "J8") (pin "33") (pinfunction "PFI_8/P2.0_33") (pintype "passive"))
      (node (ref "R100") (pin "2") (pinfunction "2_2") (pintype "passive"))
      (node (ref "U8") (pin "4") (pinfunction "A2_4") (pintype "passive"))
    )
    (net (code "36") (name "/ECHO_A_2") (class "Default")
      (node (ref "J8") (pin "37") (pinfunction "PFI_10/P2.2_37") (pintype "passive"))
      (node (ref "R108") (pin "2") (pinfunction "2_2") (pintype "passive"))
      (node (ref "U8") (pin "6") (pinfunction "A4_6") (pintype "passive"))
    )
    (net (code "37") (name "/ECHO_A_3") (class "Default")
      (node (ref "J8") (pin "26") (pinfunction "D_GND_26") (pintype "passive"))
      (node (ref "R99") (pin "2") (pinfunction "2_2") (pintype "passive"))
      (node (ref "U8") (pin "8") (pinfunction "A6_8") (pintype "passive"))
    )
    (net (code "38") (name "/ECHO_A_4") (class "Default")
      (node (ref "J8") (pin "22") (pinfunction "D_GND_22") (pintype "passive"))
      (node (ref "R107") (pin "2") (pinfunction "2_2") (pintype "passive"))
      (node (ref "U8") (pin "10") (pinfunction "A8_10") (pintype "passive"))
    )
    (net (code "39") (name "/ECHO_B_1") (class "Default")
      (node (ref "DS1") (pin "2") (pinfunction "2_2") (pintype "passive"))
      (node (ref "R105") (pin "2") (pinfunction "2_2") (pintype "passive"))
      (node (ref "U8") (pin "17") (pinfunction "B2_17") (pintype "passive"))
    )
    (net (code "40") (name "/ECHO_B_2") (class "Default")
      (node (ref "DS2") (pin "2") (pinfunction "2_2") (pintype "passive"))
      (node (ref "R98") (pin "2") (pinfunction "2_2") (pintype "passive"))
      (node (ref "U8") (pin "15") (pinfunction "B4_15") (pintype "passive"))
    )
    (net (code "41") (name "/ECHO_B_3") (class "Default")
      (node (ref "DS3") (pin "2") (pinfunction "2_2") (pintype "passive"))
      (node (ref "R106") (pin "2") (pinfunction "2_2") (pintype "passive"))
      (node (ref "U8") (pin "13") (pinfunction "B6_13") (pintype "passive"))
    )
    (net (code "42") (name "/ECHO_B_4") (class "Default")
      (node (ref "DS4") (pin "2") (pinfunction "2_2") (pintype "passive"))
      (node (ref "R97") (pin "2") (pinfunction "2_2") (pintype "passive"))
      (node (ref "U8") (pin "11") (pinfunction "B8_11") (pintype "passive"))
    )
    (net (code "44") (name "/ENABLE1") (class "Default")
      (node (ref "U2") (pin "3") (pinfunction "D3_3") (pintype "passive"))
    )
    (net (code "45") (name "/ENABLE2") (class "Default")
      (node (ref "U2") (pin "5") (pinfunction "D5_5") (pintype "passive"))
    )
    (net (code "46") (name "/ENABLE3") (class "Default")
      (node (ref "U2") (pin "6") (pinfunction "D6_6") (pintype "passive"))
    )
    (net (code "47") (name "/ENABLE4") (class "Default")
      (node (ref "U2") (pin "9") (pinfunction "D9_9") (pintype "passive"))
    )
    (net (code "49") (name "/IMU_INT") (class "Default")
      (node (ref "J8") (pin "18") (pinfunction "D_GND_18") (pintype "passive"))
      (node (ref "U11") (pin "6") (pinfunction "INT_6") (pintype "passive"))
    )
    (net (code "50") (name "/IMU_RST") (class "Default")
      (node (ref "J8") (pin "16") (pinfunction "D_GND_16") (pintype "passive"))
      (node (ref "U11") (pin "7") (pinfunction "RST_7") (pintype "passive"))
    )
    (net (code "51") (name "/LED0") (class "Default")
      (node (ref "LED0") (pin "A") (pinfunction "A_A") (pintype "passive"))
      (node (ref "U4") (pin "11") (pinfunction "LED5_11") (pintype "passive"))
    )
    (net (code "52") (name "/LED1") (class "Default")
      (node (ref "LED1") (pin "A") (pinfunction "A_A") (pintype "passive"))
      (node (ref "U4") (pin "12") (pinfunction "LED6_12") (pintype "passive"))
    )
    (net (code "53") (name "/LED2") (class "Default")
      (node (ref "LED2") (pin "A") (pinfunction "A_A") (pintype "passive"))
      (node (ref "U4") (pin "13") (pinfunction "LED7_13") (pintype "passive"))
    )
    (net (code "54") (name "/LED3") (class "Default")
      (node (ref "LED3") (pin "A") (pinfunction "A_A") (pintype "passive"))
      (node (ref "U4") (pin "15") (pinfunction "LED8_15") (pintype "passive"))
    )
    (net (code "55") (name "/LED4") (class "Default")
      (node (ref "LED4") (pin "A") (pinfunction "A_A") (pintype "passive"))
      (node (ref "U4") (pin "16") (pinfunction "LED9_16") (pintype "passive"))
    )
    (net (code "56") (name "/LED5") (class "Default")
      (node (ref "LED5") (pin "A") (pinfunction "A_A") (pintype "passive"))
      (node (ref "U4") (pin "17") (pinfunction "LED10_17") (pintype "passive"))
    )
    (net (code "57") (name "/LED6") (class "Default")
      (node (ref "LED6") (pin "A") (pinfunction "A_A") (pintype "passive"))
      (node (ref "U4") (pin "18") (pinfunction "LED11_18") (pintype "passive"))
    )
    (net (code "58") (name "/LED7") (class "Default")
      (node (ref "LED7") (pin "A") (pinfunction "A_A") (pintype "passive"))
      (node (ref "U4") (pin "19") (pinfunction "LED12_19") (pintype "passive"))
    )
    (net (code "59") (name "/NetLabel100") (class "Default")
      (node (ref "U2") (pin "7") (pinfunction "D7_7") (pintype "passive"))
    )
    (net (code "60") (name "/NetLabel101") (class "Default")
      (node (ref "U2") (pin "8") (pinfunction "D8_8") (pintype "passive"))
    )
    (net (code "62") (name "/PHASE1") (class "Default")
      (node (ref "U3") (pin "4") (pinfunction "IO0_4") (pintype "passive"))
    )
    (net (code "63") (name "/PHASE2") (class "Default")
      (node (ref "U3") (pin "5") (pinfunction "IO1_5") (pintype "passive"))
    )
    (net (code "64") (name "/PHASE3") (class "Default")
      (node (ref "U3") (pin "6") (pinfunction "IO2_6") (pintype "passive"))
    )
    (net (code "65") (name "/PHASE4") (class "Default")
      (node (ref "U3") (pin "7") (pinfunction "IO3_7") (pintype "passive"))
    )
    (net (code "67") (name "/RXD") (class "Default")
      (node (ref "J8") (pin "10") (pinfunction "D_GND_10") (pintype "passive"))
      (node (ref "U2") (pin "TXD") (pinfunction "TXD_TXD") (pintype "passive"))
    )
    (net (code "68") (name "/SCL") (class "Default")
      (node (ref "SCL") (pin "1") (pintype "passive"))
      (node (ref "SCL_R") (pin "2") (pinfunction "2_2") (pintype "passive"))
      (node (ref "U10") (pin "14") (pinfunction "SCL_14") (pintype "passive"))
      (node (ref "U11") (pin "4") (pinfunction "SCL_4") (pintype "passive"))
      (node (ref "U2") (pin "A5") (pinfunction "A5/D19_A5") (pintype "passive"))
      (node (ref "U3") (pin "14") (pinfunction "SCL_14") (pintype "passive"))
      (node (ref "U4") (pin "26") (pinfunction "SCL_26") (pintype "passive"))
    )
    (net (code "69") (name "/SCL1") (class "Default")
      (node (ref "J8") (pin "5") (pinfunction "P0.2_5") (pintype "passive"))
      (node (ref "SCL") (pin "2") (pintype "passive"))
    )
    (net (code "70") (name "/SDA") (class "Default")
      (node (ref "SDA") (pin "1") (pintype "passive"))
      (node (ref "SDA_R") (pin "2") (pinfunction "2_2") (pintype "passive"))
      (node (ref "U10") (pin "15") (pinfunction "SDA_15") (pintype "passive"))
      (node (ref "U11") (pin "5") (pinfunction "SDA_5") (pintype "passive"))
      (node (ref "U2") (pin "A4") (pinfunction "A4/D18_A4") (pintype "passive"))
      (node (ref "U3") (pin "15") (pinfunction "SDA_15") (pintype "passive"))
      (node (ref "U4") (pin "27") (pinfunction "SDA_27") (pintype "passive"))
    )
    (net (code "71") (name "/SDA1") (class "Default")
      (node (ref "J8") (pin "3") (pinfunction "P0.1_3") (pintype "passive"))
      (node (ref "SDA") (pin "2") (pintype "passive"))
    )
    (net (code "72") (name "/SERVO_0") (class "Default")
      (node (ref "R111") (pin "2") (pinfunction "2_2") (pintype "passive"))
      (node (ref "U4") (pin "6") (pinfunction "LED0_6") (pintype "passive"))
      (node (ref "U7") (pin "3") (pinfunction "A1_3") (pintype "passive"))
    )
    (net (code "73") (name "/SERVO_1") (class "Default")
      (node (ref "R113") (pin "2") (pinfunction "2_2") (pintype "passive"))
      (node (ref "U4") (pin "7") (pinfunction "LED1_7") (pintype "passive"))
      (node (ref "U7") (pin "4") (pinfunction "A2_4") (pintype "passive"))
    )
    (net (code "74") (name "/SERVO_2") (class "Default")
      (node (ref "R115") (pin "2") (pinfunction "2_2") (pintype "passive"))
      (node (ref "U4") (pin "8") (pinfunction "LED2_8") (pintype "passive"))
      (node (ref "U7") (pin "5") (pinfunction "A3_5") (pintype "passive"))
    )
    (net (code "75") (name "/SERVO_3") (class "Default")
      (node (ref "R119") (pin "2") (pinfunction "2_2") (pintype "passive"))
      (node (ref "U4") (pin "9") (pinfunction "LED3_9") (pintype "passive"))
      (node (ref "U7") (pin "6") (pinfunction "A4_6") (pintype "passive"))
    )
    (net (code "76") (name "/SERVO_4") (class "Default")
      (node (ref "R117") (pin "2") (pinfunction "2_2") (pintype "passive"))
      (node (ref "U4") (pin "10") (pinfunction "LED4_10") (pintype "passive"))
      (node (ref "U7") (pin "7") (pinfunction "A5_7") (pintype "passive"))
    )
    (net (code "77") (name "/SERVO_B0") (class "Default")
      (node (ref "R118") (pin "2") (pinfunction "2_2") (pintype "passive"))
      (node (ref "SRV0") (pin "2") (pinfunction "2_2") (pintype "passive"))
      (node (ref "U7") (pin "18") (pinfunction "B1_18") (pintype "passive"))
    )
    (net (code "78") (name "/SERVO_B1") (class "Default")
      (node (ref "R120") (pin "2") (pinfunction "2_2") (pintype "passive"))
      (node (ref "SRV1") (pin "2") (pinfunction "2_2") (pintype "passive"))
      (node (ref "U7") (pin "17") (pinfunction "B2_17") (pintype "passive"))
    )
    (net (code "79") (name "/SERVO_B2") (class "Default")
      (node (ref "R116") (pin "2") (pinfunction "2_2") (pintype "passive"))
      (node (ref "SRV2") (pin "2") (pinfunction "2_2") (pintype "passive"))
      (node (ref "U7") (pin "16") (pinfunction "B3_16") (pintype "passive"))
    )
    (net (code "80") (name "/SERVO_B3") (class "Default")
      (node (ref "R114") (pin "2") (pinfunction "2_2") (pintype "passive"))
      (node (ref "SRV3") (pin "2") (pinfunction "2_2") (pintype "passive"))
      (node (ref "U7") (pin "15") (pinfunction "B4_15") (pintype "passive"))
    )
    (net (code "81") (name "/SERVO_B4") (class "Default")
      (node (ref "R112") (pin "2") (pinfunction "2_2") (pintype "passive"))
      (node (ref "SRV4") (pin "2") (pinfunction "2_2") (pintype "passive"))
      (node (ref "U7") (pin "14") (pinfunction "B5_14") (pintype "passive"))
    )
    (net (code "82") (name "/SW0") (class "Default")
      (node (ref "C14") (pin "1") (pintype "passive"))
      (node (ref "J8") (pin "7") (pinfunction "P0.3_7") (pintype "passive"))
      (node (ref "R16") (pin "2") (pinfunction "2_2") (pintype "passive"))
    )
    (net (code "83") (name "/SW1") (class "Default")
      (node (ref "C18") (pin "1") (pintype "passive"))
      (node (ref "J8") (pin "11") (pinfunction "P0.5_11") (pintype "passive"))
      (node (ref "R26") (pin "2") (pinfunction "2_2") (pintype "passive"))
    )
    (net (code "84") (name "/SW2") (class "Default")
      (node (ref "C19") (pin "1") (pintype "passive"))
      (node (ref "J8") (pin "13") (pinfunction "P0.6_13") (pintype "passive"))
      (node (ref "R30") (pin "2") (pinfunction "2_2") (pintype "passive"))
    )
    (net (code "85") (name "/SW3") (class "Default")
      (node (ref "C27") (pin "1") (pintype "passive"))
      (node (ref "J8") (pin "15") (pinfunction "P0.7_15") (pintype "passive"))
      (node (ref "R35") (pin "2") (pinfunction "2_2") (pintype "passive"))
    )
    (net (code "86") (name "/SW4") (class "Default")
      (node (ref "C28") (pin "1") (pintype "passive"))
      (node (ref "J8") (pin "19") (pinfunction "PFI_1/P1.1_19") (pintype "passive"))
      (node (ref "R42") (pin "2") (pinfunction "2_2") (pintype "passive"))
    )
    (net (code "87") (name "/SW5") (class "Default")
      (node (ref "C29") (pin "1") (pintype "passive"))
      (node (ref "J8") (pin "21") (pinfunction "PFI_2/P1.2_21") (pintype "passive"))
      (node (ref "R46") (pin "2") (pinfunction "2_2") (pintype "passive"))
    )
    (net (code "88") (name "/SW6") (class "Default")
      (node (ref "C30") (pin "1") (pintype "passive"))
      (node (ref "J8") (pin "23") (pinfunction "PFI_3/P1.3_23") (pintype "passive"))
      (node (ref "R49") (pin "2") (pinfunction "2_2") (pintype "passive"))
    )
    (net (code "89") (name "/SW7") (class "Default")
      (node (ref "C34") (pin "1") (pintype "passive"))
      (node (ref "J8") (pin "29") (pinfunction "PFI_6/P1.6_29") (pintype "passive"))
      (node (ref "R53") (pin "2") (pinfunction "2_2") (pintype "passive"))
    )
    (net (code "90") (name "/SWO1") (class "Default")
      (node (ref "Q6") (pin "3") (pinfunction "D_3") (pintype "passive"))
      (node (ref "SW1") (pin "1") (pinfunction "1_1") (pintype "passive"))
    )
    (net (code "91") (name "/SWO2") (class "Default")
      (node (ref "Q7") (pin "3") (pinfunction "D_3") (pintype "passive"))
      (node (ref "SW2") (pin "1") (pinfunction "1_1") (pintype "passive"))
    )
    (net (code "92") (name "/SWO3") (class "Default")
      (node (ref "Q8") (pin "3") (pinfunction "D_3") (pintype "passive"))
      (node (ref "SW3") (pin "1") (pinfunction "1_1") (pintype "passive"))
    )
    (net (code "93") (name "/SWO4") (class "Default")
      (node (ref "Q9") (pin "3") (pinfunction "D_3") (pintype "passive"))
      (node (ref "SW4") (pin "1") (pinfunction "1_1") (pintype "passive"))
    )
    (net (code "94") (name "/TRIG_A_1") (class "Default")
      (node (ref "J8") (pin "31") (pinfunction "PFI_7/P1.7_31") (pintype "passive"))
      (node (ref "R95") (pin "2") (pinfunction "2_2") (pintype "passive"))
      (node (ref "U8") (pin "3") (pinfunction "A1_3") (pintype "passive"))
    )
    (net (code "95") (name "/TRIG_A_2") (class "Default")
      (node (ref "J8") (pin "35") (pinfunction "PFI_9/P2.1_35") (pintype "passive"))
      (node (ref "R104") (pin "2") (pinfunction "2_2") (pintype "passive"))
      (node (ref "U8") (pin "5") (pinfunction "A3_5") (pintype "passive"))
    )
    (net (code "96") (name "/TRIG_A_3") (class "Default")
      (node (ref "J8") (pin "32") (pinfunction "D_GND_32") (pintype "passive"))
      (node (ref "R96") (pin "2") (pinfunction "2_2") (pintype "passive"))
      (node (ref "U8") (pin "7") (pinfunction "A5_7") (pintype "passive"))
    )
    (net (code "97") (name "/TRIG_A_4") (class "Default")
      (node (ref "J8") (pin "24") (pinfunction "D_GND_24") (pintype "passive"))
      (node (ref "R103") (pin "2") (pinfunction "2_2") (pintype "passive"))
      (node (ref "U8") (pin "9") (pinfunction "A7_9") (pintype "passive"))
    )
    (net (code "98") (name "/TRIG_B_1") (class "Default")
      (node (ref "DS1") (pin "3") (pinfunction "3_3") (pintype "passive"))
      (node (ref "R109") (pin "2") (pinfunction "2_2") (pintype "passive"))
      (node (ref "U8") (pin "18") (pinfunction "B1_18") (pintype "passive"))
    )
    (net (code "99") (name "/TRIG_B_2") (class "Default")
      (node (ref "DS2") (pin "3") (pinfunction "3_3") (pintype "passive"))
      (node (ref "R101") (pin "2") (pinfunction "2_2") (pintype "passive"))
      (node (ref "U8") (pin "16") (pinfunction "B3_16") (pintype "passive"))
    )
    (net (code "100") (name "/TRIG_B_3") (class "Default")
      (node (ref "DS3") (pin "3") (pinfunction "3_3") (pintype "passive"))
      (node (ref "R110") (pin "2") (pinfunction "2_2") (pintype "passive"))
      (node (ref "U8") (pin "14") (pinfunction "B5_14") (pintype "passive"))
    )
    (net (code "101") (name "/TRIG_B_4") (class "Default")
      (node (ref "DS4") (pin "3") (pinfunction "3_3") (pintype "passive"))
      (node (ref "R102") (pin "2") (pinfunction "2_2") (pintype "passive"))
      (node (ref "U8") (pin "12") (pinfunction "B7_12") (pintype "passive"))
    )
    (net (code "102") (name "/TXD") (class "Default")
      (node (ref "J8") (pin "8") (pinfunction "D_GND_8") (pintype "passive"))
      (node (ref "U2") (pin "RXD") (pinfunction "RXD_RXD") (pintype "passive"))
    )
    (net (code "104") (name "GND") (class "Default")
      (node (ref "AD1") (pin "3") (pinfunction "3_3") (pintype "passive"))
      (node (ref "AD2") (pin "3") (pinfunction "3_3") (pintype "passive"))
      (node (ref "AD3") (pin "3") (pinfunction "3_3") (pintype "passive"))
      (node (ref "AD4") (pin "3") (pinfunction "3_3") (pintype "passive"))
      (node (ref "C14") (pin "2") (pintype "passive"))
      (node (ref "C15") (pin "2") (pintype "passive"))
      (node (ref "C16") (pin "2") (pintype "passive"))
      (node (ref "C17") (pin "2") (pintype "passive"))
      (node (ref "C18") (pin "2") (pintype "passive"))
      (node (ref "C19") (pin "2") (pintype "passive"))
      (node (ref "C20") (pin "1") (pintype "passive"))
      (node (ref "C21") (pin "1") (pintype "passive"))
      (node (ref "C22") (pin "1") (pintype "passive"))
      (node (ref "C23") (pin "-") (pinfunction "-_-") (pintype "passive"))
      (node (ref "C24") (pin "-") (pinfunction "-_-") (pintype "passive"))
      (node (ref "C25") (pin "-") (pinfunction "-_-") (pintype "passive"))
      (node (ref "C26") (pin "-") (pinfunction "-_-") (pintype "passive"))
      (node (ref "C27") (pin "2") (pintype "passive"))
      (node (ref "C28") (pin "2") (pintype "passive"))
      (node (ref "C29") (pin "2") (pintype "passive"))
      (node (ref "C30") (pin "2") (pintype "passive"))
      (node (ref "C31") (pin "2") (pintype "passive"))
      (node (ref "C32") (pin "2") (pintype "passive"))
      (node (ref "C33") (pin "2") (pintype "passive"))
      (node (ref "C34") (pin "2") (pintype "passive"))
      (node (ref "C42") (pin "2") (pintype "passive"))
      (node (ref "C44") (pin "2") (pintype "passive"))
      (node (ref "C45") (pin "2") (pintype "passive"))
      (node (ref "C46") (pin "2") (pintype "passive"))
      (node (ref "C47") (pin "2") (pintype "passive"))
      (node (ref "C48") (pin "2") (pintype "passive"))
      (node (ref "C49") (pin "2") (pintype "passive"))
      (node (ref "C50") (pin "2") (pintype "passive"))
      (node (ref "C51") (pin "2") (pintype "passive"))
      (node (ref "C52") (pin "2") (pintype "passive"))
      (node (ref "C53") (pin "2") (pintype "passive"))
      (node (ref "C54") (pin "2") (pintype "passive"))
      (node (ref "C56") (pin "1") (pintype "passive"))
      (node (ref "C58") (pin "2") (pintype "passive"))
      (node (ref "C59") (pin "2") (pintype "passive"))
      (node (ref "C60") (pin "2") (pintype "passive"))
      (node (ref "C61") (pin "2") (pintype "passive"))
      (node (ref "C62") (pin "2") (pintype "passive"))
      (node (ref "C63") (pin "2") (pintype "passive"))
      (node (ref "C64") (pin "2") (pintype "passive"))
      (node (ref "C65") (pin "2") (pintype "passive"))
      (node (ref "C66") (pin "2") (pintype "passive"))
      (node (ref "C67") (pin "2") (pintype "passive"))
      (node (ref "C68") (pin "2") (pintype "passive"))
      (node (ref "D2") (pin "1") (pinfunction "1_1") (pintype "passive"))
      (node (ref "D3") (pin "1") (pinfunction "1_1") (pintype "passive"))
      (node (ref "D4") (pin "1") (pinfunction "1_1") (pintype "passive"))
      (node (ref "D5") (pin "1") (pinfunction "1_1") (pintype "passive"))
      (node (ref "D6") (pin "1") (pinfunction "1_1") (pintype "passive"))
      (node (ref "D7") (pin "1") (pinfunction "1_1") (pintype "passive"))
      (node (ref "D8") (pin "1") (pinfunction "1_1") (pintype "passive"))
      (node (ref "D9") (pin "1") (pinfunction "1_1") (pintype "passive"))
      (node (ref "DS1") (pin "1") (pinfunction "1_1") (pintype "passive"))
      (node (ref "DS2") (pin "1") (pinfunction "1_1") (pintype "passive"))
      (node (ref "DS3") (pin "1") (pinfunction "1_1") (pintype "passive"))
      (node (ref "DS4") (pin "1") (pinfunction "1_1") (pintype "passive"))
      (node (ref "J8") (pin "14") (pinfunction "D_GND_14") (pintype "passive"))
      (node (ref "J8") (pin "20") (pinfunction "D_GND_20") (pintype "passive"))
      (node (ref "J8") (pin "25") (pinfunction "PFI_4/P1.4_25") (pintype "passive"))
      (node (ref "J8") (pin "30") (pinfunction "D_GND_30") (pintype "passive"))
      (node (ref "J8") (pin "34") (pinfunction "D_GND_34") (pintype "passive"))
      (node (ref "J8") (pin "39") (pinfunction "PFI_11/P2.3_39") (pintype "passive"))
      (node (ref "J8") (pin "6") (pinfunction "D_GND_6") (pintype "passive"))
      (node (ref "J8") (pin "9") (pinfunction "P0.4_9") (pintype "passive"))
      (node (ref "MTR1") (pin "4") (pintype "passive"))
      (node (ref "MTR2") (pin "4") (pintype "passive"))
      (node (ref "MTR3") (pin "4") (pintype "passive"))
      (node (ref "MTR4") (pin "4") (pintype "passive"))
      (node (ref "Q6") (pin "2") (pinfunction "S_2") (pintype "passive"))
      (node (ref "Q7") (pin "2") (pinfunction "S_2") (pintype "passive"))
      (node (ref "Q8") (pin "2") (pinfunction "S_2") (pintype "passive"))
      (node (ref "Q9") (pin "2") (pinfunction "S_2") (pintype "passive"))
      (node (ref "R17") (pin "2") (pinfunction "2_2") (pintype "passive"))
      (node (ref "R24") (pin "2") (pinfunction "2_2") (pintype "passive"))
      (node (ref "R27") (pin "2") (pinfunction "2_2") (pintype "passive"))
      (node (ref "R31") (pin "2") (pinfunction "2_2") (pintype "passive"))
      (node (ref "R33") (pin "2") (pinfunction "2_2") (pintype "passive"))
      (node (ref "R36") (pin "2") (pinfunction "2_2") (pintype "passive"))
      (node (ref "R37") (pin "2") (pinfunction "2_2") (pintype "passive"))
      (node (ref "R38") (pin "2") (pinfunction "2_2") (pintype "passive"))
      (node (ref "R39") (pin "2") (pinfunction "2_2") (pintype "passive"))
      (node (ref "R43") (pin "2") (pinfunction "2_2") (pintype "passive"))
      (node (ref "R55") (pin "2") (pinfunction "2_2") (pintype "passive"))
      (node (ref "R56") (pin "2") (pinfunction "2_2") (pintype "passive"))
      (node (ref "R57") (pin "2") (pinfunction "2_2") (pintype "passive"))
      (node (ref "R58") (pin "2") (pinfunction "2_2") (pintype "passive"))
      (node (ref "R59") (pin "2") (pinfunction "2_2") (pintype "passive"))
      (node (ref "R60") (pin "2") (pinfunction "2_2") (pintype "passive"))
      (node (ref "R61") (pin "2") (pinfunction "2_2") (pintype "passive"))
      (node (ref "R65") (pin "2") (pinfunction "2_2") (pintype "passive"))
      (node (ref "R66") (pin "2") (pinfunction "2_2") (pintype "passive"))
      (node (ref "R71") (pin "2") (pinfunction "2_2") (pintype "passive"))
      (node (ref "R72") (pin "2") (pinfunction "2_2") (pintype "passive"))
      (node (ref "R73") (pin "2") (pinfunction "2_2") (pintype "passive"))
      (node (ref "R74") (pin "2") (pinfunction "2_2") (pintype "passive"))
      (node (ref "R75") (pin "2") (pinfunction "2_2") (pintype "passive"))
      (node (ref "S0") (pin "1") (pintype "passive"))
      (node (ref "S0") (pin "2") (pintype "passive"))
      (node (ref "S1") (pin "1") (pintype "passive"))
      (node (ref "S1") (pin "2") (pintype "passive"))
      (node (ref "S2") (pin "1") (pintype "passive"))
      (node (ref "S2") (pin "2") (pintype "passive"))
      (node (ref "S3") (pin "1") (pintype "passive"))
      (node (ref "S3") (pin "2") (pintype "passive"))
      (node (ref "S4") (pin "1") (pintype "passive"))
      (node (ref "S4") (pin "2") (pintype "passive"))
      (node (ref "S5") (pin "1") (pintype "passive"))
      (node (ref "S5") (pin "2") (pintype "passive"))
      (node (ref "S6") (pin "1") (pintype "passive"))
      (node (ref "S6") (pin "2") (pintype "passive"))
      (node (ref "S7") (pin "1") (pintype "passive"))
      (node (ref "S7") (pin "2") (pintype "passive"))
      (node (ref "SRV0") (pin "1") (pinfunction "1_1") (pintype "passive"))
      (node (ref "SRV1") (pin "1") (pinfunction "1_1") (pintype "passive"))
      (node (ref "SRV2") (pin "1") (pinfunction "1_1") (pintype "passive"))
      (node (ref "SRV3") (pin "1") (pinfunction "1_1") (pintype "passive"))
      (node (ref "SRV4") (pin "1") (pinfunction "1_1") (pintype "passive"))
      (node (ref "U10") (pin "11") (pinfunction "COM_11") (pintype "passive"))
      (node (ref "U10") (pin "9") (pinfunction "GND_9") (pintype "passive"))
      (node (ref "U11") (pin "1") (pinfunction "GND_1") (pintype "passive"))
      (node (ref "U11") (pin "10") (pinfunction "GND_10") (pintype "passive"))
      (node (ref "U11") (pin "8") (pinfunction "GND_8") (pintype "passive"))
      (node (ref "U11") (pin "9") (pinfunction "GND_9") (pintype "passive"))
      (node (ref "U2") (pin "GND") (pinfunction "GND_GND") (pintype "passive"))
      (node (ref "U3") (pin "8") (pinfunction "GND_8") (pintype "passive"))
      (node (ref "U4") (pin "14") (pinfunction "Vss_14") (pintype "passive"))
      (node (ref "U4") (pin "25") (pinfunction "EXTCLK_25") (pintype "passive"))
      (node (ref "U7") (pin "1") (pinfunction "GND_1") (pintype "passive"))
      (node (ref "U8") (pin "1") (pinfunction "GND_1") (pintype "passive"))
      (node (ref "U9") (pin "1") (pinfunction "GND_1") (pintype "passive"))
    )
    (net (code "105") (name "Net-(C53-Pad1)") (class "Default")
      (node (ref "C53") (pin "1") (pintype "passive"))
      (node (ref "R13") (pin "1") (pinfunction "1_1") (pintype "passive"))
      (node (ref "U2") (pin "A6") (pinfunction "A6_A6") (pintype "passive"))
    )
    (net (code "106") (name "Net-(C54-Pad1)") (class "Default")
      (node (ref "C54") (pin "1") (pintype "passive"))
      (node (ref "R10") (pin "1") (pinfunction "1_1") (pintype "passive"))
      (node (ref "U2") (pin "A7") (pinfunction "A7_A7") (pintype "passive"))
    )
    (net (code "107") (name "Net-(D2-Pad3)") (class "Default")
      (node (ref "D2") (pin "3") (pinfunction "3_3") (pintype "passive"))
      (node (ref "R15") (pin "2") (pinfunction "2_2") (pintype "passive"))
      (node (ref "R16") (pin "1") (pinfunction "1_1") (pintype "passive"))
    )
    (net (code "108") (name "Net-(D3-Pad3)") (class "Default")
      (node (ref "D3") (pin "3") (pinfunction "3_3") (pintype "passive"))
      (node (ref "R25") (pin "2") (pinfunction "2_2") (pintype "passive"))
      (node (ref "R26") (pin "1") (pinfunction "1_1") (pintype "passive"))
    )
    (net (code "109") (name "Net-(D4-Pad3)") (class "Default")
      (node (ref "D4") (pin "3") (pinfunction "3_3") (pintype "passive"))
      (node (ref "R29") (pin "2") (pinfunction "2_2") (pintype "passive"))
      (node (ref "R30") (pin "1") (pinfunction "1_1") (pintype "passive"))
    )
    (net (code "110") (name "Net-(D5-Pad3)") (class "Default")
      (node (ref "D5") (pin "3") (pinfunction "3_3") (pintype "passive"))
      (node (ref "R34") (pin "2") (pinfunction "2_2") (pintype "passive"))
      (node (ref "R35") (pin "1") (pinfunction "1_1") (pintype "passive"))
    )
    (net (code "111") (name "Net-(D6-Pad3)") (class "Default")
      (node (ref "D6") (pin "3") (pinfunction "3_3") (pintype "passive"))
      (node (ref "R41") (pin "2") (pinfunction "2_2") (pintype "passive"))
      (node (ref "R42") (pin "1") (pinfunction "1_1") (pintype "passive"))
    )
    (net (code "112") (name "Net-(D7-Pad3)") (class "Default")
      (node (ref "D7") (pin "3") (pinfunction "3_3") (pintype "passive"))
      (node (ref "R45") (pin "2") (pinfunction "2_2") (pintype "passive"))
      (node (ref "R46") (pin "1") (pinfunction "1_1") (pintype "passive"))
    )
    (net (code "113") (name "Net-(D8-Pad3)") (class "Default")
      (node (ref "D8") (pin "3") (pinfunction "3_3") (pintype "passive"))
      (node (ref "R48") (pin "2") (pinfunction "2_2") (pintype "passive"))
      (node (ref "R49") (pin "1") (pinfunction "1_1") (pintype "passive"))
    )
    (net (code "114") (name "Net-(D9-Pad3)") (class "Default")
      (node (ref "D9") (pin "3") (pinfunction "3_3") (pintype "passive"))
      (node (ref "R52") (pin "2") (pinfunction "2_2") (pintype "passive"))
      (node (ref "R53") (pin "1") (pinfunction "1_1") (pintype "passive"))
    )
    (net (code "115") (name "Net-(LED0-PadK)") (class "Default")
      (node (ref "LED0") (pin "K") (pinfunction "K_K") (pintype "passive"))
      (node (ref "R55") (pin "1") (pinfunction "1_1") (pintype "passive"))
    )
    (net (code "116") (name "Net-(LED1-PadK)") (class "Default")
      (node (ref "LED1") (pin "K") (pinfunction "K_K") (pintype "passive"))
      (node (ref "R56") (pin "1") (pinfunction "1_1") (pintype "passive"))
    )
    (net (code "117") (name "Net-(LED2-PadK)") (class "Default")
      (node (ref "LED2") (pin "K") (pinfunction "K_K") (pintype "passive"))
      (node (ref "R57") (pin "1") (pinfunction "1_1") (pintype "passive"))
    )
    (net (code "118") (name "Net-(LED3-PadK)") (class "Default")
      (node (ref "LED3") (pin "K") (pinfunction "K_K") (pintype "passive"))
      (node (ref "R58") (pin "1") (pinfunction "1_1") (pintype "passive"))
    )
    (net (code "119") (name "Net-(LED4-PadK)") (class "Default")
      (node (ref "LED4") (pin "K") (pinfunction "K_K") (pintype "passive"))
      (node (ref "R59") (pin "1") (pinfunction "1_1") (pintype "passive"))
    )
    (net (code "120") (name "Net-(LED5-PadK)") (class "Default")
      (node (ref "LED5") (pin "K") (pinfunction "K_K") (pintype "passive"))
      (node (ref "R60") (pin "1") (pinfunction "1_1") (pintype "passive"))
    )
    (net (code "121") (name "Net-(LED6-PadK)") (class "Default")
      (node (ref "LED6") (pin "K") (pinfunction "K_K") (pintype "passive"))
      (node (ref "R61") (pin "1") (pinfunction "1_1") (pintype "passive"))
    )
    (net (code "122") (name "Net-(LED7-PadK)") (class "Default")
      (node (ref "LED7") (pin "K") (pinfunction "K_K") (pintype "passive"))
      (node (ref "R75") (pin "1") (pinfunction "1_1") (pintype "passive"))
    )
    (net (code "123") (name "Net-(Q6-G)") (class "Default")
      (node (ref "Q6") (pin "1") (pinfunction "G_1") (pintype "passive"))
      (node (ref "R74") (pin "1") (pinfunction "1_1") (pintype "passive"))
      (node (ref "U3") (pin "9") (pinfunction "IO4_9") (pintype "passive"))
    )
    (net (code "124") (name "Net-(Q7-G)") (class "Default")
      (node (ref "Q7") (pin "1") (pinfunction "G_1") (pintype "passive"))
      (node (ref "R73") (pin "1") (pinfunction "1_1") (pintype "passive"))
      (node (ref "U3") (pin "10") (pinfunction "IO5_10") (pintype "passive"))
    )
    (net (code "125") (name "Net-(Q8-G)") (class "Default")
      (node (ref "Q8") (pin "1") (pinfunction "G_1") (pintype "passive"))
      (node (ref "R72") (pin "1") (pinfunction "1_1") (pintype "passive"))
      (node (ref "U3") (pin "11") (pinfunction "IO6_11") (pintype "passive"))
    )
    (net (code "126") (name "Net-(Q9-G)") (class "Default")
      (node (ref "Q9") (pin "1") (pinfunction "G_1") (pintype "passive"))
      (node (ref "R71") (pin "1") (pinfunction "1_1") (pintype "passive"))
      (node (ref "U3") (pin "12") (pinfunction "IO7_12") (pintype "passive"))
    )
    (net (code "127") (name "Net-(R14-Pad2)") (class "Default")
      (node (ref "R14") (pin "2") (pinfunction "2_2") (pintype "passive"))
      (node (ref "R15") (pin "1") (pinfunction "1_1") (pintype "passive"))
      (node (ref "S0") (pin "3") (pintype "passive"))
      (node (ref "S0") (pin "4") (pintype "passive"))
    )
    (net (code "128") (name "Net-(R18-Pad2)") (class "Default")
      (node (ref "R18") (pin "2") (pinfunction "2_2") (pintype "passive"))
      (node (ref "R25") (pin "1") (pinfunction "1_1") (pintype "passive"))
      (node (ref "S1") (pin "3") (pintype "passive"))
      (node (ref "S1") (pin "4") (pintype "passive"))
    )
    (net (code "129") (name "Net-(R28-Pad2)") (class "Default")
      (node (ref "R28") (pin "2") (pinfunction "2_2") (pintype "passive"))
      (node (ref "R29") (pin "1") (pinfunction "1_1") (pintype "passive"))
      (node (ref "S2") (pin "3") (pintype "passive"))
      (node (ref "S2") (pin "4") (pintype "passive"))
    )
    (net (code "130") (name "Net-(R32-Pad2)") (class "Default")
      (node (ref "R32") (pin "2") (pinfunction "2_2") (pintype "passive"))
      (node (ref "R34") (pin "1") (pinfunction "1_1") (pintype "passive"))
      (node (ref "S3") (pin "3") (pintype "passive"))
      (node (ref "S3") (pin "4") (pintype "passive"))
    )
    (net (code "131") (name "Net-(R40-Pad2)") (class "Default")
      (node (ref "R40") (pin "2") (pinfunction "2_2") (pintype "passive"))
      (node (ref "R41") (pin "1") (pinfunction "1_1") (pintype "passive"))
      (node (ref "S4") (pin "3") (pintype "passive"))
      (node (ref "S4") (pin "4") (pintype "passive"))
    )
    (net (code "132") (name "Net-(R44-Pad2)") (class "Default")
      (node (ref "R44") (pin "2") (pinfunction "2_2") (pintype "passive"))
      (node (ref "R45") (pin "1") (pinfunction "1_1") (pintype "passive"))
      (node (ref "S5") (pin "3") (pintype "passive"))
      (node (ref "S5") (pin "4") (pintype "passive"))
    )
    (net (code "133") (name "Net-(R47-Pad2)") (class "Default")
      (node (ref "R47") (pin "2") (pinfunction "2_2") (pintype "passive"))
      (node (ref "R48") (pin "1") (pinfunction "1_1") (pintype "passive"))
      (node (ref "S6") (pin "3") (pintype "passive"))
      (node (ref "S6") (pin "4") (pintype "passive"))
    )
    (net (code "134") (name "Net-(R51-Pad2)") (class "Default")
      (node (ref "R51") (pin "2") (pinfunction "2_2") (pintype "passive"))
      (node (ref "R52") (pin "1") (pinfunction "1_1") (pintype "passive"))
      (node (ref "S7") (pin "3") (pintype "passive"))
      (node (ref "S7") (pin "4") (pintype "passive"))
    )
    (net (code "135") (name "Net-(U2-A2{slash}D16)") (class "Default")
      (node (ref "C51") (pin "1") (pintype "passive"))
      (node (ref "R63") (pin "1") (pinfunction "1_1") (pintype "passive"))
      (node (ref "U2") (pin "A2") (pinfunction "A2/D16_A2") (pintype "passive"))
    )
    (net (code "136") (name "Net-(U2-A3{slash}D17)") (class "Default")
      (node (ref "C52") (pin "1") (pintype "passive"))
      (node (ref "R62") (pin "1") (pinfunction "1_1") (pintype "passive"))
      (node (ref "U2") (pin "A3") (pinfunction "A3/D17_A3") (pintype "passive"))
    )
    (net (code "137") (name "Net-(U3-A0)") (class "Default")
      (node (ref "A0_IO") (pin "1") (pintype "passive"))
      (node (ref "R27") (pin "1") (pinfunction "1_1") (pintype "passive"))
      (node (ref "U3") (pin "1") (pinfunction "A0_1") (pintype "passive"))
    )
    (net (code "138") (name "Net-(U3-A1)") (class "Default")
      (node (ref "A1_IO") (pin "1") (pintype "passive"))
      (node (ref "R24") (pin "1") (pinfunction "1_1") (pintype "passive"))
      (node (ref "U3") (pin "2") (pinfunction "A1_2") (pintype "passive"))
    )
    (net (code "139") (name "Net-(U3-A2)") (class "Default")
      (node (ref "A2_IO") (pin "1") (pintype "passive"))
      (node (ref "R17") (pin "1") (pinfunction "1_1") (pintype "passive"))
      (node (ref "U3") (pin "3") (pinfunction "A2_3") (pintype "passive"))
    )
    (net (code "140") (name "Net-(U4-A0)") (class "Default")
      (node (ref "A0_PWM") (pin "1") (pintype "passive"))
      (node (ref "R31") (pin "1") (pinfunction "1_1") (pintype "passive"))
      (node (ref "U4") (pin "1") (pinfunction "A0_1") (pintype "passive"))
    )
    (net (code "141") (name "Net-(U4-A1)") (class "Default")
      (node (ref "A1_PWM") (pin "1") (pintype "passive"))
      (node (ref "R33") (pin "1") (pinfunction "1_1") (pintype "passive"))
      (node (ref "U4") (pin "2") (pinfunction "A1_2") (pintype "passive"))
    )
    (net (code "142") (name "Net-(U4-A2)") (class "Default")
      (node (ref "A2_PWM") (pin "1") (pintype "passive"))
      (node (ref "R36") (pin "1") (pinfunction "1_1") (pintype "passive"))
      (node (ref "U4") (pin "3") (pinfunction "A2_3") (pintype "passive"))
    )
    (net (code "143") (name "Net-(U4-A3)") (class "Default")
      (node (ref "A3_PWM") (pin "1") (pintype "passive"))
      (node (ref "R37") (pin "1") (pinfunction "1_1") (pintype "passive"))
      (node (ref "U4") (pin "4") (pinfunction "A3_4") (pintype "passive"))
    )
    (net (code "144") (name "Net-(U4-A4)") (class "Default")
      (node (ref "A4_PWM") (pin "1") (pintype "passive"))
      (node (ref "R39") (pin "1") (pinfunction "1_1") (pintype "passive"))
      (node (ref "U4") (pin "5") (pinfunction "A4_5") (pintype "passive"))
    )
    (net (code "145") (name "Net-(U4-A5)") (class "Default")
      (node (ref "A5_PWM") (pin "1") (pintype "passive"))
      (node (ref "R38") (pin "1") (pinfunction "1_1") (pintype "passive"))
      (node (ref "U4") (pin "24") (pinfunction "A5_24") (pintype "passive"))
    )
    (net (code "146") (name "Net-(U4-OE)") (class "Default")
      (node (ref "OE_PWM") (pin "1") (pintype "passive"))
      (node (ref "R43") (pin "1") (pinfunction "1_1") (pintype "passive"))
      (node (ref "U4") (pin "23") (pinfunction "OE_23") (pintype "passive"))
    )
    (net (code "147") (name "Net-(U7-EN)") (class "Default")
      (node (ref "C44") (pin "1") (pintype "passive"))
      (node (ref "R50") (pin "1") (pinfunction "1_1") (pintype "passive"))
      (node (ref "U7") (pin "19") (pinfunction "VREFB_19") (pintype "passive"))
      (node (ref "U7") (pin "20") (pinfunction "EN_20") (pintype "passive"))
    )
    (net (code "148") (name "Net-(U8-EN)") (class "Default")
      (node (ref "C49") (pin "1") (pintype "passive"))
      (node (ref "R9") (pin "1") (pinfunction "1_1") (pintype "passive"))
      (node (ref "U8") (pin "19") (pinfunction "VREFB_19") (pintype "passive"))
      (node (ref "U8") (pin "20") (pinfunction "EN_20") (pintype "passive"))
    )
    (net (code "149") (name "Net-(U9-B1)") (class "Default")
      (node (ref "MTR4") (pin "6") (pintype "passive"))
      (node (ref "R82") (pin "2") (pinfunction "2_2") (pintype "passive"))
      (node (ref "U9") (pin "18") (pinfunction "B1_18") (pintype "passive"))
    )
    (net (code "150") (name "Net-(U9-B2)") (class "Default")
      (node (ref "MTR4") (pin "8") (pintype "passive"))
      (node (ref "R86") (pin "2") (pinfunction "2_2") (pintype "passive"))
      (node (ref "U9") (pin "17") (pinfunction "B2_17") (pintype "passive"))
    )
    (net (code "151") (name "Net-(U9-B3)") (class "Default")
      (node (ref "MTR3") (pin "6") (pintype "passive"))
      (node (ref "R90") (pin "2") (pinfunction "2_2") (pintype "passive"))
      (node (ref "U9") (pin "16") (pinfunction "B3_16") (pintype "passive"))
    )
    (net (code "152") (name "Net-(U9-B4)") (class "Default")
      (node (ref "MTR3") (pin "8") (pintype "passive"))
      (node (ref "R93") (pin "2") (pinfunction "2_2") (pintype "passive"))
      (node (ref "U9") (pin "15") (pinfunction "B4_15") (pintype "passive"))
    )
    (net (code "153") (name "Net-(U9-B5)") (class "Default")
      (node (ref "MTR2") (pin "6") (pintype "passive"))
      (node (ref "R81") (pin "2") (pinfunction "2_2") (pintype "passive"))
      (node (ref "U9") (pin "14") (pinfunction "B5_14") (pintype "passive"))
    )
    (net (code "154") (name "Net-(U9-B6)") (class "Default")
      (node (ref "MTR2") (pin "8") (pintype "passive"))
      (node (ref "R85") (pin "2") (pinfunction "2_2") (pintype "passive"))
      (node (ref "U9") (pin "13") (pinfunction "B6_13") (pintype "passive"))
    )
    (net (code "155") (name "Net-(U9-B7)") (class "Default")
      (node (ref "MTR1") (pin "6") (pintype "passive"))
      (node (ref "R89") (pin "2") (pinfunction "2_2") (pintype "passive"))
      (node (ref "U9") (pin "12") (pinfunction "B7_12") (pintype "passive"))
    )
    (net (code "156") (name "Net-(U9-B8)") (class "Default")
      (node (ref "MTR1") (pin "8") (pintype "passive"))
      (node (ref "R94") (pin "2") (pinfunction "2_2") (pintype "passive"))
      (node (ref "U9") (pin "11") (pinfunction "B8_11") (pintype "passive"))
    )
    (net (code "157") (name "Net-(U9-EN)") (class "Default")
      (node (ref "C59") (pin "1") (pintype "passive"))
      (node (ref "R64") (pin "1") (pinfunction "1_1") (pintype "passive"))
      (node (ref "U9") (pin "19") (pinfunction "VREFB_19") (pintype "passive"))
      (node (ref "U9") (pin "20") (pinfunction "EN_20") (pintype "passive"))
    )
    (net (code "158") (name "Net-(U10-A0)") (class "Default")
      (node (ref "A0_AD") (pin "2") (pintype "passive"))
      (node (ref "R66") (pin "1") (pinfunction "1_1") (pintype "passive"))
      (node (ref "U10") (pin "12") (pinfunction "A0_12") (pintype "passive"))
    )
    (net (code "159") (name "Net-(U10-A1)") (class "Default")
      (node (ref "A1_AD") (pin "2") (pintype "passive"))
      (node (ref "R65") (pin "1") (pinfunction "1_1") (pintype "passive"))
      (node (ref "U10") (pin "13") (pinfunction "A1_13") (pintype "passive"))
    )
    (net (code "160") (name "Net-(U10-CH0)") (class "Default")
      (node (ref "C68") (pin "1") (pintype "passive"))
      (node (ref "R67") (pin "2") (pinfunction "2_2") (pintype "passive"))
      (node (ref "U10") (pin "1") (pinfunction "CH0_1") (pintype "passive"))
    )
    (net (code "161") (name "Net-(U10-CH1)") (class "Default")
      (node (ref "C67") (pin "1") (pintype "passive"))
      (node (ref "R68") (pin "2") (pinfunction "2_2") (pintype "passive"))
      (node (ref "U10") (pin "2") (pinfunction "CH1_2") (pintype "passive"))
    )
    (net (code "162") (name "Net-(U10-CH2)") (class "Default")
      (node (ref "C66") (pin "1") (pintype "passive"))
      (node (ref "R69") (pin "2") (pinfunction "2_2") (pintype "passive"))
      (node (ref "U10") (pin "3") (pinfunction "CH2_3") (pintype "passive"))
    )
    (net (code "163") (name "Net-(U10-CH3)") (class "Default")
      (node (ref "C65") (pin "1") (pintype "passive"))
      (node (ref "R70") (pin "2") (pinfunction "2_2") (pintype "passive"))
      (node (ref "U10") (pin "4") (pinfunction "CH3_4") (pintype "passive"))
    )
    (net (code "164") (name "unconnected-(J8-D_GND-Pad12)") (class "Default")
      (node (ref "J8") (pin "12") (pinfunction "D_GND_12") (pintype "passive"))
    )
    (net (code "165") (name "unconnected-(J8-D_GND-Pad28)") (class "Default")
      (node (ref "J8") (pin "28") (pinfunction "D_GND_28") (pintype "passive"))
    )
    (net (code "166") (name "unconnected-(J8-D_GND-Pad36)") (class "Default")
      (node (ref "J8") (pin "36") (pinfunction "D_GND_36") (pintype "passive"))
    )
    (net (code "167") (name "unconnected-(J8-D_GND-Pad38)") (class "Default")
      (node (ref "J8") (pin "38") (pinfunction "D_GND_38") (pintype "passive"))
    )
    (net (code "168") (name "unconnected-(J8-D_GND-Pad40)") (class "Default")
      (node (ref "J8") (pin "40") (pinfunction "D_GND_40") (pintype "passive"))
    )
    (net (code "169") (name "unconnected-(J8-P0.0-Pad1)") (class "Default")
      (node (ref "J8") (pin "1") (pinfunction "P0.0_1") (pintype "passive"))
    )
    (net (code "170") (name "unconnected-(J8-PFI_0{slash}P1.0-Pad17)") (class "Default")
      (node (ref "J8") (pin "17") (pinfunction "PFI_0/P1.0_17") (pintype "passive"))
    )
    (net (code "171") (name "unconnected-(J8-PFI_5{slash}P1.5-Pad27)") (class "Default")
      (node (ref "J8") (pin "27") (pinfunction "PFI_5/P1.5_27") (pintype "passive"))
    )
    (net (code "172") (name "unconnected-(U2-PadRAW)") (class "Default")
      (node (ref "U2") (pin "RAW") (pinfunction "RAW_RAW") (pintype "passive"))
    )
    (net (code "173") (name "unconnected-(U2-Reset-PadRST1)") (class "Default")
      (node (ref "U2") (pin "RST1") (pinfunction "Reset_RST1") (pintype "passive"))
    )
    (net (code "174") (name "unconnected-(U2-Reset-PadRST2)") (class "Default")
      (node (ref "U2") (pin "RST2") (pinfunction "Reset_RST2") (pintype "passive"))
    )
    (net (code "175") (name "unconnected-(U3-INT-Pad13)") (class "Default")
      (node (ref "U3") (pin "13") (pinfunction "INT_13") (pintype "passive"))
    )
    (net (code "176") (name "unconnected-(U4-LED13-Pad20)") (class "Default")
      (node (ref "U4") (pin "20") (pinfunction "LED13_20") (pintype "passive"))
    )
    (net (code "177") (name "unconnected-(U4-LED14-Pad21)") (class "Default")
      (node (ref "U4") (pin "21") (pinfunction "LED14_21") (pintype "passive"))
    )
    (net (code "178") (name "unconnected-(U4-LED15-Pad22)") (class "Default")
      (node (ref "U4") (pin "22") (pinfunction "LED15_22") (pintype "passive"))
    )
    (net (code "179") (name "unconnected-(U7-A6-Pad8)") (class "Default")
      (node (ref "U7") (pin "8") (pinfunction "A6_8") (pintype "passive"))
    )
    (net (code "180") (name "unconnected-(U7-A7-Pad9)") (class "Default")
      (node (ref "U7") (pin "9") (pinfunction "A7_9") (pintype "passive"))
    )
    (net (code "181") (name "unconnected-(U7-A8-Pad10)") (class "Default")
      (node (ref "U7") (pin "10") (pinfunction "A8_10") (pintype "passive"))
    )
    (net (code "182") (name "unconnected-(U7-B6-Pad13)") (class "Default")
      (node (ref "U7") (pin "13") (pinfunction "B6_13") (pintype "passive"))
    )
    (net (code "183") (name "unconnected-(U7-B7-Pad12)") (class "Default")
      (node (ref "U7") (pin "12") (pinfunction "B7_12") (pintype "passive"))
    )
    (net (code "184") (name "unconnected-(U7-B8-Pad11)") (class "Default")
      (node (ref "U7") (pin "11") (pinfunction "B8_11") (pintype "passive"))
    )
    (net (code "185") (name "unconnected-(U10-CH4-Pad5)") (class "Default")
      (node (ref "U10") (pin "5") (pinfunction "CH4_5") (pintype "passive"))
    )
    (net (code "186") (name "unconnected-(U10-CH5-Pad6)") (class "Default")
      (node (ref "U10") (pin "6") (pinfunction "CH5_6") (pintype "passive"))
    )
    (net (code "187") (name "unconnected-(U10-CH6-Pad7)") (class "Default")
      (node (ref "U10") (pin "7") (pinfunction "CH6_7") (pintype "passive"))
    )
    (net (code "188") (name "unconnected-(U10-CH7-Pad8)") (class "Default")
      (node (ref "U10") (pin "8") (pinfunction "CH7_8") (pintype "passive"))
    )
    (net (code "189") (name "unconnected-(U11-BOOT-Pad3)") (class "Default")
      (node (ref "U11") (pin "3") (pinfunction "BOOT_3") (pintype "passive"))
    )
  )
)
